# Controller_Rev_2.net
KiCad netlist of a schematic drawn in EAGLE
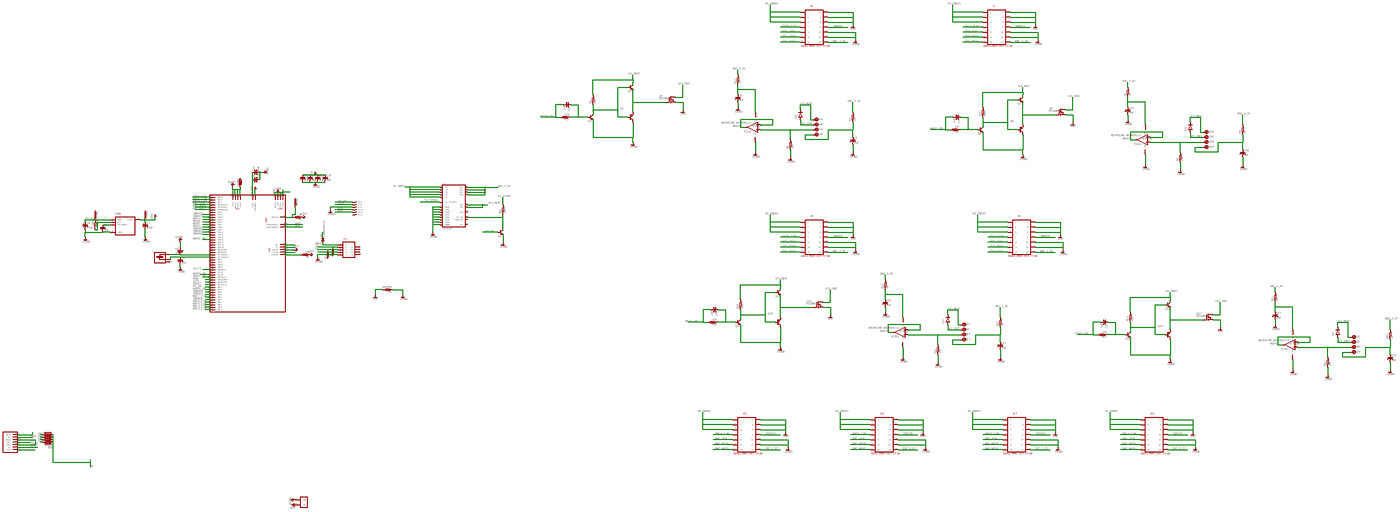
[diagram p0: schematic, sheet 1, overview]
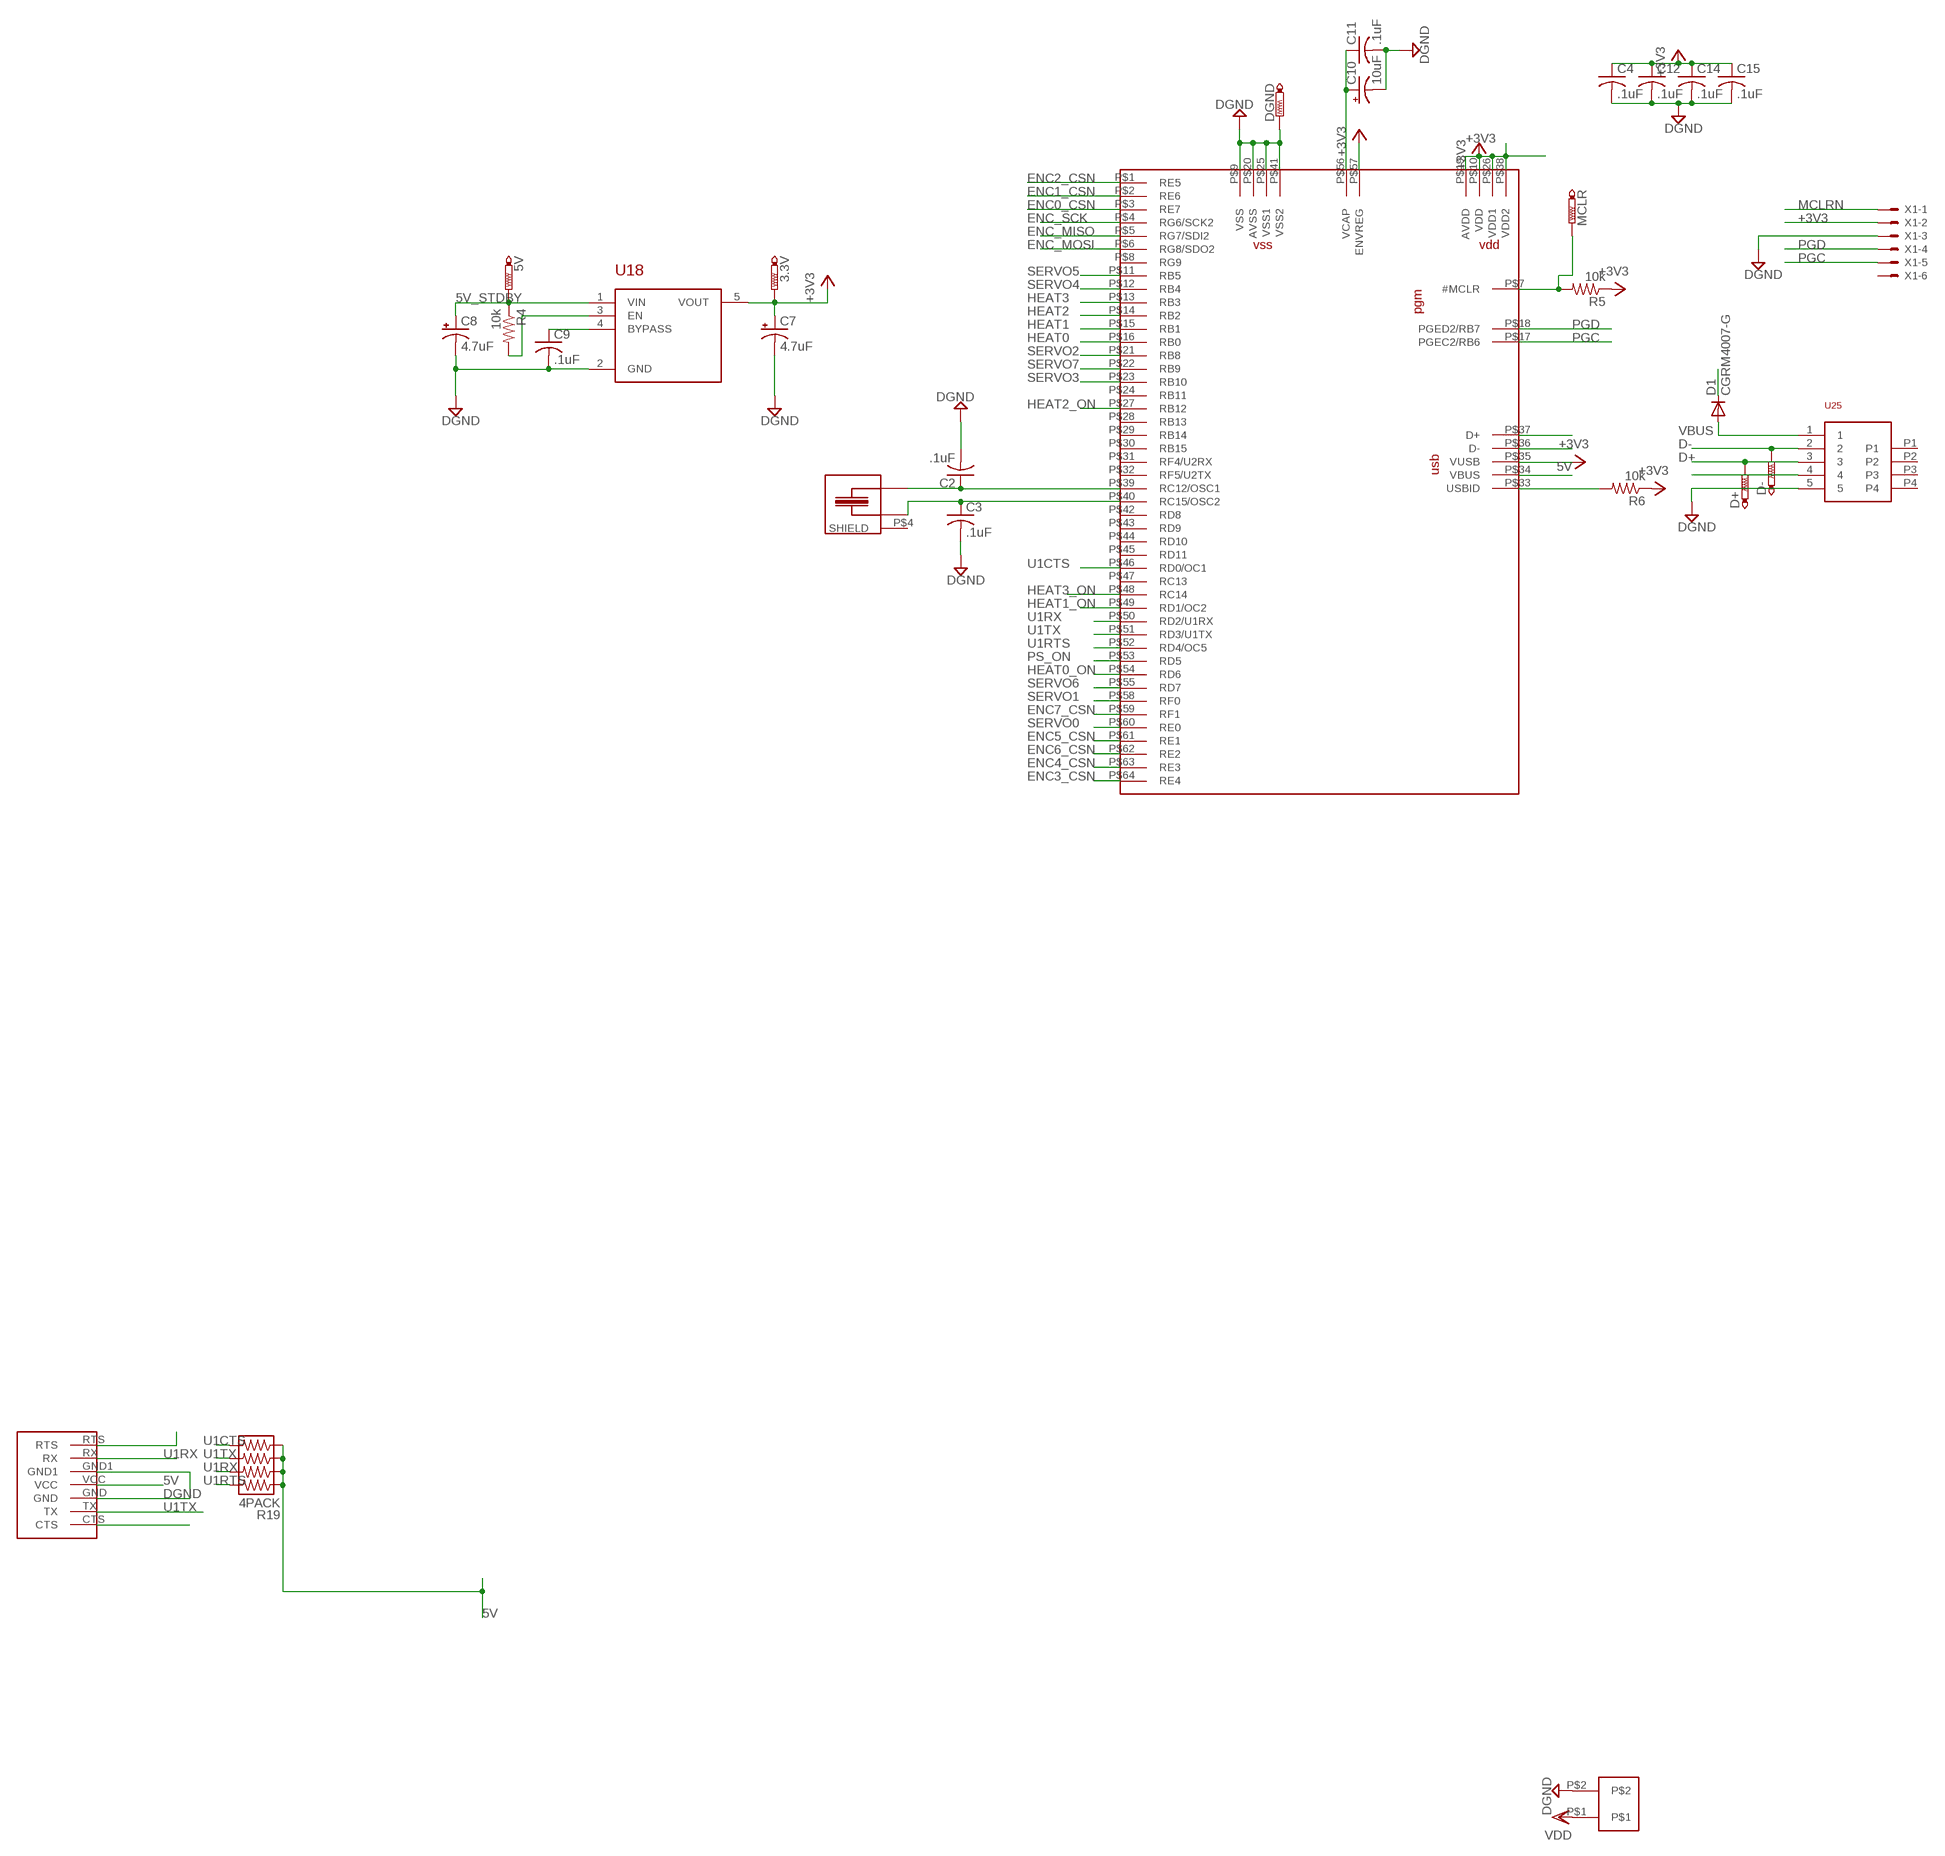
[diagram p1: schematic, sheet 1, part 1 of 4]
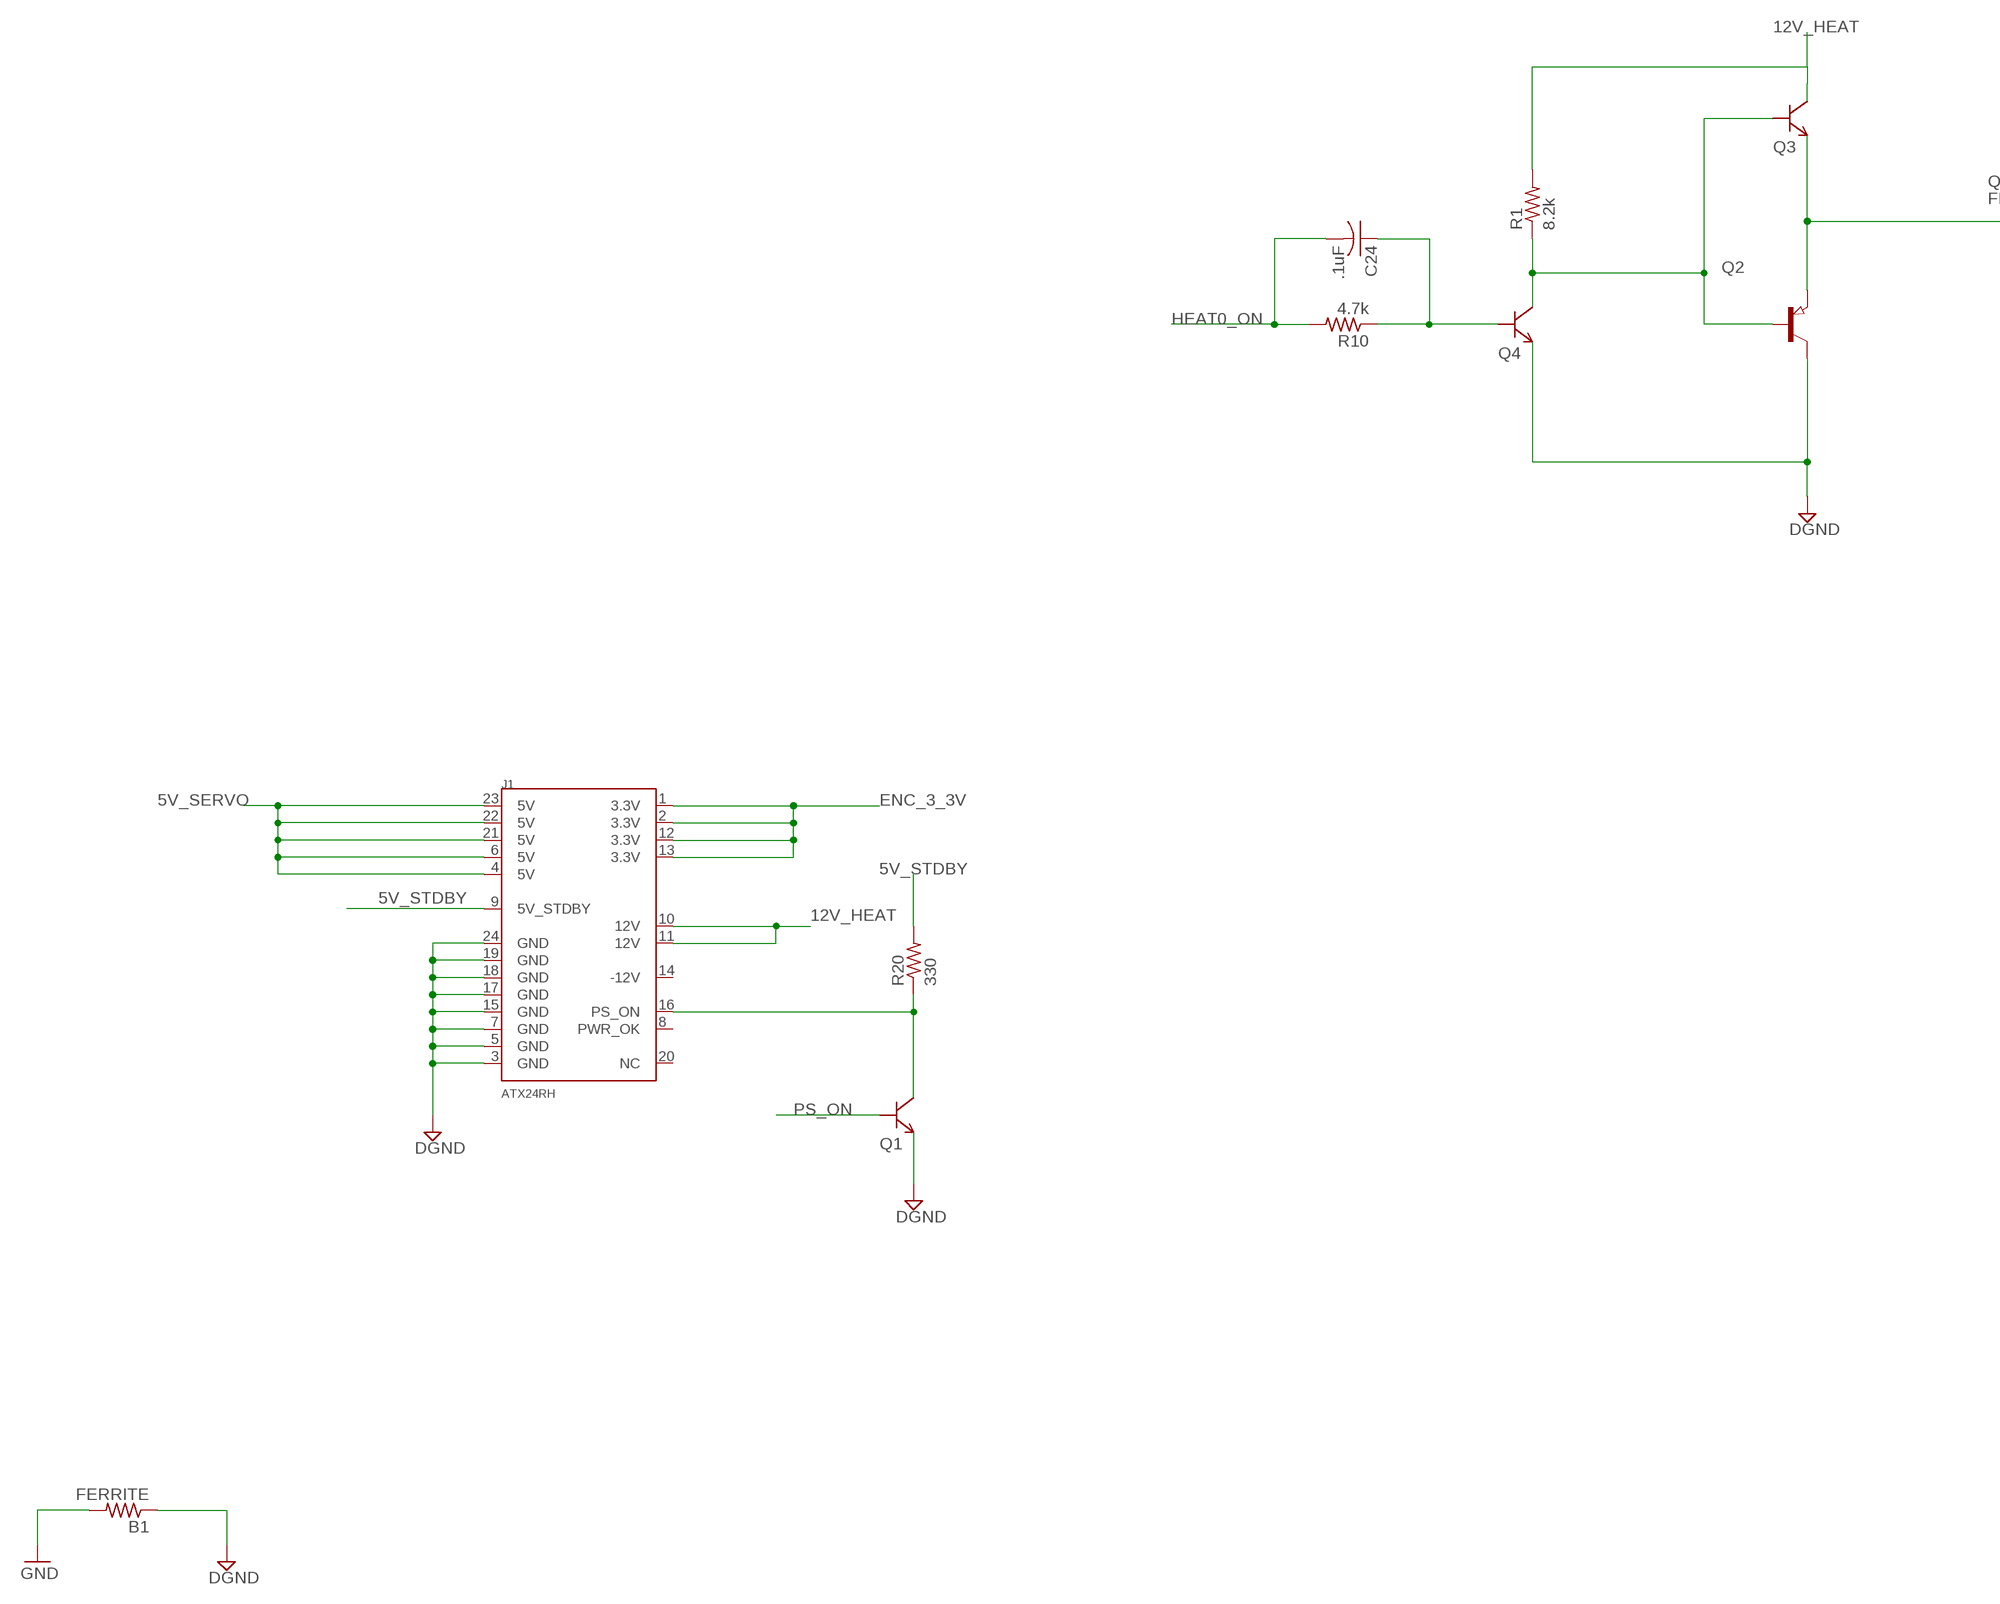
[diagram p2: schematic, sheet 1, part 2 of 4]
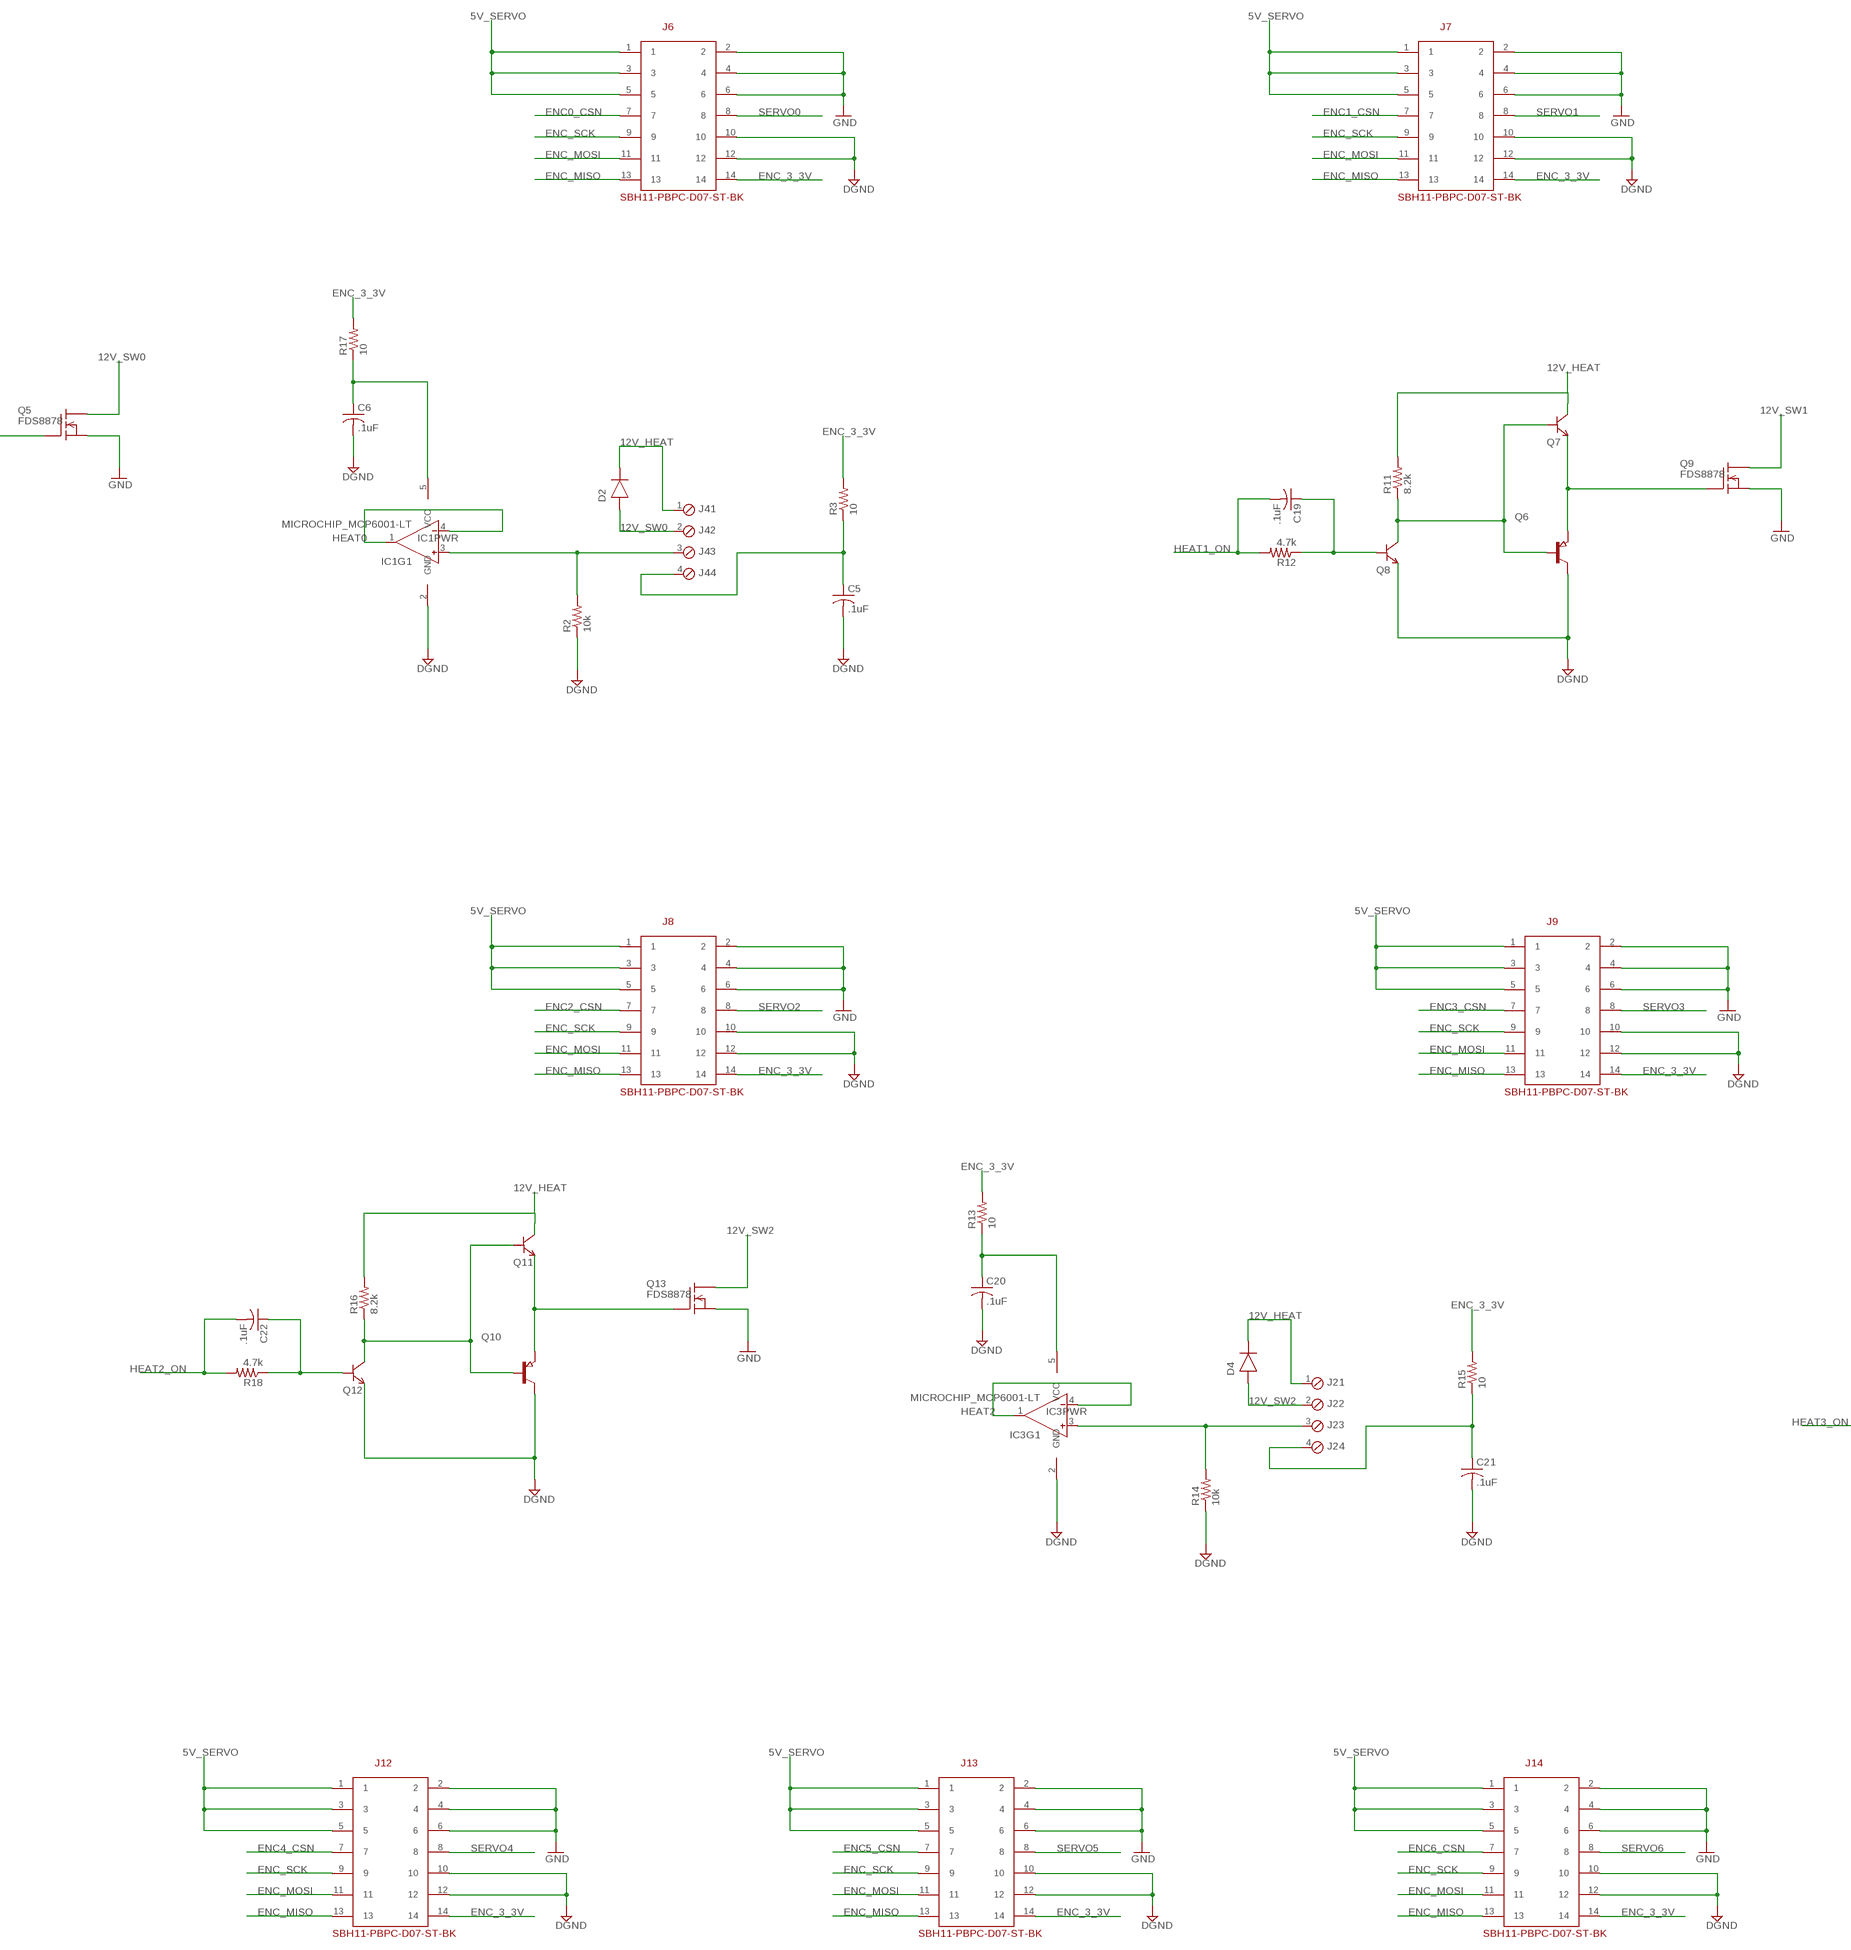
[diagram p3: schematic, sheet 1, part 3 of 4]
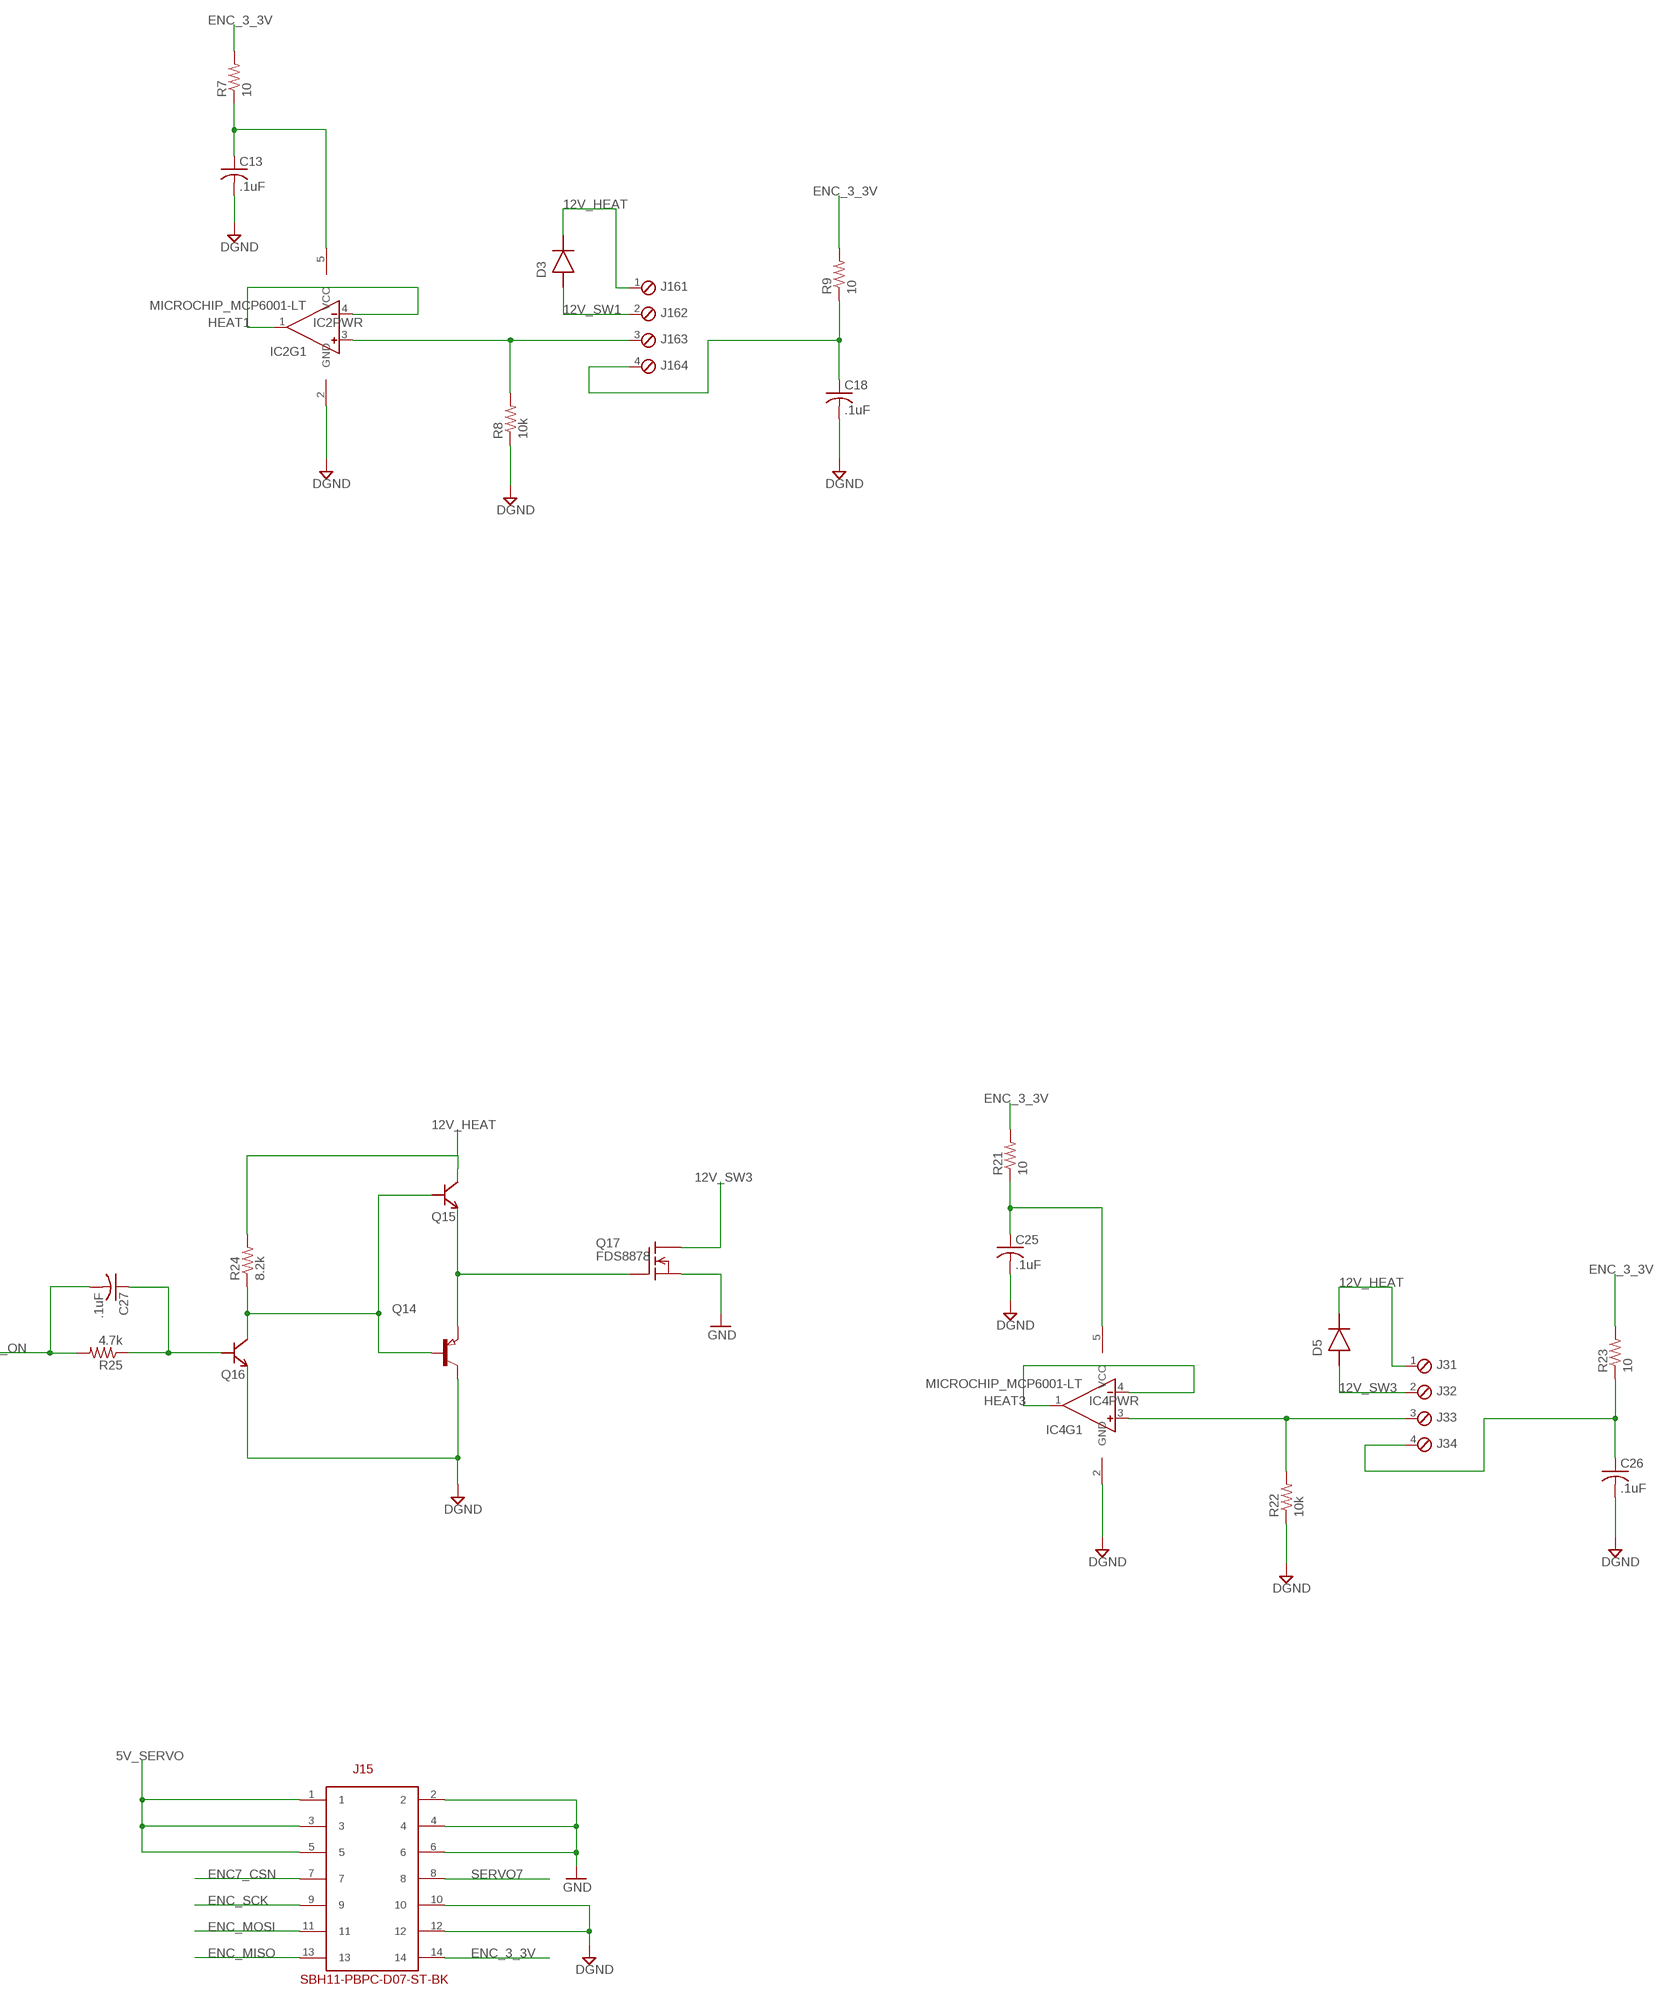
[diagram p4: schematic, sheet 1, part 4 of 4]

(export (version "E")
  (design (tool "Eeschema 10.0.6"))
  (components
    (comp (ref "3.3V")
      (value "PTR1TP14R")
      (footprint "eagle-import:TP14R")
      (libsource (lib "eagle-import") (part "PTR1TP14R"))
    )
    (comp (ref "5V")
      (value "PTR1TP14R")
      (footprint "eagle-import:TP14R")
      (libsource (lib "eagle-import") (part "PTR1TP14R"))
    )
    (comp (ref "B1")
      (value "FERRITE")
      (footprint "eagle-import:R0603")
      (libsource (lib "eagle-import") (part "R-US_R0603"))
    )
    (comp (ref "C2")
      (value ".1uF")
      (footprint "eagle-import:C0603")
      (libsource (lib "eagle-import") (part "C-USC0603"))
    )
    (comp (ref "C3")
      (value ".1uF")
      (footprint "eagle-import:C0603")
      (libsource (lib "eagle-import") (part "C-USC0603"))
    )
    (comp (ref "C4")
      (value ".1uF")
      (footprint "eagle-import:C0603")
      (libsource (lib "eagle-import") (part "C-USC0603"))
    )
    (comp (ref "C5")
      (value ".1uF")
      (footprint "eagle-import:C0603")
      (libsource (lib "eagle-import") (part "C-USC0603"))
    )
    (comp (ref "C6")
      (value ".1uF")
      (footprint "eagle-import:C0603")
      (libsource (lib "eagle-import") (part "C-USC0603"))
    )
    (comp (ref "C7")
      (value "4.7uF")
      (footprint "eagle-import:R_2012-12R")
      (libsource (lib "eagle-import") (part "CPOL-USR/2012-12R"))
    )
    (comp (ref "C8")
      (value "4.7uF")
      (footprint "eagle-import:R_2012-12R")
      (libsource (lib "eagle-import") (part "CPOL-USR/2012-12R"))
    )
    (comp (ref "C9")
      (value ".1uF")
      (footprint "eagle-import:C0402")
      (libsource (lib "eagle-import") (part "C-USC0402"))
    )
    (comp (ref "C10")
      (value "10uF")
      (footprint "eagle-import:R_2012-12R")
      (libsource (lib "eagle-import") (part "CPOL-USR/2012-12R"))
    )
    (comp (ref "C11")
      (value ".1uF")
      (footprint "eagle-import:C0603")
      (libsource (lib "eagle-import") (part "C-USC0603"))
    )
    (comp (ref "C12")
      (value ".1uF")
      (footprint "eagle-import:C0603")
      (libsource (lib "eagle-import") (part "C-USC0603"))
    )
    (comp (ref "C13")
      (value ".1uF")
      (footprint "eagle-import:C0603")
      (libsource (lib "eagle-import") (part "C-USC0603"))
    )
    (comp (ref "C14")
      (value ".1uF")
      (footprint "eagle-import:C0603")
      (libsource (lib "eagle-import") (part "C-USC0603"))
    )
    (comp (ref "C15")
      (value ".1uF")
      (footprint "eagle-import:C0603")
      (libsource (lib "eagle-import") (part "C-USC0603"))
    )
    (comp (ref "C18")
      (value ".1uF")
      (footprint "eagle-import:C0603")
      (libsource (lib "eagle-import") (part "C-USC0603"))
    )
    (comp (ref "C19")
      (value ".1uF")
      (footprint "eagle-import:C0603")
      (libsource (lib "eagle-import") (part "C-USC0603"))
    )
    (comp (ref "C20")
      (value ".1uF")
      (footprint "eagle-import:C0603")
      (libsource (lib "eagle-import") (part "C-USC0603"))
    )
    (comp (ref "C21")
      (value ".1uF")
      (footprint "eagle-import:C0603")
      (libsource (lib "eagle-import") (part "C-USC0603"))
    )
    (comp (ref "C22")
      (value ".1uF")
      (footprint "eagle-import:C0603")
      (libsource (lib "eagle-import") (part "C-USC0603"))
    )
    (comp (ref "C24")
      (value ".1uF")
      (footprint "eagle-import:C0603")
      (libsource (lib "eagle-import") (part "C-USC0603"))
    )
    (comp (ref "C25")
      (value ".1uF")
      (footprint "eagle-import:C0603")
      (libsource (lib "eagle-import") (part "C-USC0603"))
    )
    (comp (ref "C26")
      (value ".1uF")
      (footprint "eagle-import:C0603")
      (libsource (lib "eagle-import") (part "C-USC0603"))
    )
    (comp (ref "C27")
      (value ".1uF")
      (footprint "eagle-import:C0603")
      (libsource (lib "eagle-import") (part "C-USC0603"))
    )
    (comp (ref "D+")
      (value "PTR1TP14R")
      (footprint "eagle-import:TP14R")
      (libsource (lib "eagle-import") (part "PTR1TP14R"))
    )
    (comp (ref "D-")
      (value "PTR1TP14R")
      (footprint "eagle-import:TP14R")
      (libsource (lib "eagle-import") (part "PTR1TP14R"))
    )
    (comp (ref "D1")
      (value "CGRM4007-G")
      (footprint "eagle-import:SOD-123_MINI-SMA")
      (libsource (lib "eagle-import") (part "CGRM400-G7"))
    )
    (comp (ref "D2")
      (value "DISCRETE_DIODESMA")
      (footprint "eagle-import:DISCRETE_SMA")
      (libsource (lib "eagle-import") (part "DISCRETE_DIODESMA"))
    )
    (comp (ref "D3")
      (value "DISCRETE_DIODESMA")
      (footprint "eagle-import:DISCRETE_SMA")
      (libsource (lib "eagle-import") (part "DISCRETE_DIODESMA"))
    )
    (comp (ref "D4")
      (value "DISCRETE_DIODESMA")
      (footprint "eagle-import:DISCRETE_SMA")
      (libsource (lib "eagle-import") (part "DISCRETE_DIODESMA"))
    )
    (comp (ref "D5")
      (value "DISCRETE_DIODESMA")
      (footprint "eagle-import:DISCRETE_SMA")
      (libsource (lib "eagle-import") (part "DISCRETE_DIODESMA"))
    )
    (comp (ref "DGND")
      (value "PTR1B1,27")
      (footprint "eagle-import:B1,27")
      (libsource (lib "eagle-import") (part "PTR1B1,27"))
    )
    (comp (ref "IC1")
      (value "MICROCHIP_MCP6001-LT")
      (footprint "eagle-import:MICROCHIP_SC70-5-LT")
      (libsource (lib "eagle-import") (part "MICROCHIP_MCP6001-LT"))
    )
    (comp (ref "IC2")
      (value "MICROCHIP_MCP6001-LT")
      (footprint "eagle-import:MICROCHIP_SC70-5-LT")
      (libsource (lib "eagle-import") (part "MICROCHIP_MCP6001-LT"))
    )
    (comp (ref "IC3")
      (value "MICROCHIP_MCP6001-LT")
      (footprint "eagle-import:MICROCHIP_SC70-5-LT")
      (libsource (lib "eagle-import") (part "MICROCHIP_MCP6001-LT"))
    )
    (comp (ref "IC4")
      (value "MICROCHIP_MCP6001-LT")
      (footprint "eagle-import:MICROCHIP_SC70-5-LT")
      (libsource (lib "eagle-import") (part "MICROCHIP_MCP6001-LT"))
    )
    (comp (ref "J1")
      (value "ATX24RH")
      (footprint "eagle-import:ATX24_RIGHT_ANGLE")
      (libsource (lib "eagle-import") (part "ATX24RH"))
    )
    (comp (ref "J2")
      (value "OSTVN04A150")
      (footprint "eagle-import:4POL254")
      (libsource (lib "eagle-import") (part "OSTVN04A150"))
    )
    (comp (ref "J3")
      (value "OSTVN04A150")
      (footprint "eagle-import:4POL254")
      (libsource (lib "eagle-import") (part "OSTVN04A150"))
    )
    (comp (ref "J4")
      (value "OSTVN04A150")
      (footprint "eagle-import:4POL254")
      (libsource (lib "eagle-import") (part "OSTVN04A150"))
    )
    (comp (ref "J6")
      (value "SBH11-PBPC-D07-ST-BK")
      (footprint "eagle-import:SBH11-PBPC-D07-ST-BK")
      (libsource (lib "eagle-import") (part "SBH11-PBPC-D07-ST-BK"))
    )
    (comp (ref "J7")
      (value "SBH11-PBPC-D07-ST-BK")
      (footprint "eagle-import:SBH11-PBPC-D07-ST-BK")
      (libsource (lib "eagle-import") (part "SBH11-PBPC-D07-ST-BK"))
    )
    (comp (ref "J8")
      (value "SBH11-PBPC-D07-ST-BK")
      (footprint "eagle-import:SBH11-PBPC-D07-ST-BK")
      (libsource (lib "eagle-import") (part "SBH11-PBPC-D07-ST-BK"))
    )
    (comp (ref "J9")
      (value "SBH11-PBPC-D07-ST-BK")
      (footprint "eagle-import:SBH11-PBPC-D07-ST-BK")
      (libsource (lib "eagle-import") (part "SBH11-PBPC-D07-ST-BK"))
    )
    (comp (ref "J10")
      (value "WASP7PIN")
      (footprint "eagle-import:WASP7PIN")
      (libsource (lib "eagle-import") (part "WASP7PIN"))
    )
    (comp (ref "J12")
      (value "SBH11-PBPC-D07-ST-BK")
      (footprint "eagle-import:SBH11-PBPC-D07-ST-BK")
      (libsource (lib "eagle-import") (part "SBH11-PBPC-D07-ST-BK"))
    )
    (comp (ref "J13")
      (value "SBH11-PBPC-D07-ST-BK")
      (footprint "eagle-import:SBH11-PBPC-D07-ST-BK")
      (libsource (lib "eagle-import") (part "SBH11-PBPC-D07-ST-BK"))
    )
    (comp (ref "J14")
      (value "SBH11-PBPC-D07-ST-BK")
      (footprint "eagle-import:SBH11-PBPC-D07-ST-BK")
      (libsource (lib "eagle-import") (part "SBH11-PBPC-D07-ST-BK"))
    )
    (comp (ref "J15")
      (value "SBH11-PBPC-D07-ST-BK")
      (footprint "eagle-import:SBH11-PBPC-D07-ST-BK")
      (libsource (lib "eagle-import") (part "SBH11-PBPC-D07-ST-BK"))
    )
    (comp (ref "J16")
      (value "OSTVN04A150")
      (footprint "eagle-import:4POL254")
      (libsource (lib "eagle-import") (part "OSTVN04A150"))
    )
    (comp (ref "MCLR")
      (value "PTR1TP14R")
      (footprint "eagle-import:TP14R")
      (libsource (lib "eagle-import") (part "PTR1TP14R"))
    )
    (comp (ref "Q1")
      (value "DISCRETE_MMBT3904LT1G")
      (footprint "eagle-import:DISCRETE_SOT23")
      (libsource (lib "eagle-import") (part "DISCRETE_MMBT3904LT1G"))
    )
    (comp (ref "Q2")
      (value "PNP-TRANSISTOR_SOT23")
      (footprint "eagle-import:SOT23")
      (libsource (lib "eagle-import") (part "PNP-TRANSISTOR_SOT23"))
    )
    (comp (ref "Q3")
      (value "DISCRETE_MMBT3904LT1G")
      (footprint "eagle-import:DISCRETE_SOT23")
      (libsource (lib "eagle-import") (part "DISCRETE_MMBT3904LT1G"))
    )
    (comp (ref "Q4")
      (value "DISCRETE_MMBT3904LT1G")
      (footprint "eagle-import:DISCRETE_SOT23")
      (libsource (lib "eagle-import") (part "DISCRETE_MMBT3904LT1G"))
    )
    (comp (ref "Q5")
      (value "FDS8878")
      (footprint "eagle-import:SO-8")
      (libsource (lib "eagle-import") (part "FDS5680"))
    )
    (comp (ref "Q6")
      (value "PNP-TRANSISTOR_SOT23")
      (footprint "eagle-import:SOT23")
      (libsource (lib "eagle-import") (part "PNP-TRANSISTOR_SOT23"))
    )
    (comp (ref "Q7")
      (value "DISCRETE_MMBT3904LT1G")
      (footprint "eagle-import:DISCRETE_SOT23")
      (libsource (lib "eagle-import") (part "DISCRETE_MMBT3904LT1G"))
    )
    (comp (ref "Q8")
      (value "DISCRETE_MMBT3904LT1G")
      (footprint "eagle-import:DISCRETE_SOT23")
      (libsource (lib "eagle-import") (part "DISCRETE_MMBT3904LT1G"))
    )
    (comp (ref "Q9")
      (value "FDS8878")
      (footprint "eagle-import:SO-8")
      (libsource (lib "eagle-import") (part "FDS5680"))
    )
    (comp (ref "Q10")
      (value "PNP-TRANSISTOR_SOT23")
      (footprint "eagle-import:SOT23")
      (libsource (lib "eagle-import") (part "PNP-TRANSISTOR_SOT23"))
    )
    (comp (ref "Q11")
      (value "DISCRETE_MMBT3904LT1G")
      (footprint "eagle-import:DISCRETE_SOT23")
      (libsource (lib "eagle-import") (part "DISCRETE_MMBT3904LT1G"))
    )
    (comp (ref "Q12")
      (value "DISCRETE_MMBT3904LT1G")
      (footprint "eagle-import:DISCRETE_SOT23")
      (libsource (lib "eagle-import") (part "DISCRETE_MMBT3904LT1G"))
    )
    (comp (ref "Q13")
      (value "FDS8878")
      (footprint "eagle-import:SO-8")
      (libsource (lib "eagle-import") (part "FDS5680"))
    )
    (comp (ref "Q14")
      (value "PNP-TRANSISTOR_SOT23")
      (footprint "eagle-import:SOT23")
      (libsource (lib "eagle-import") (part "PNP-TRANSISTOR_SOT23"))
    )
    (comp (ref "Q15")
      (value "DISCRETE_MMBT3904LT1G")
      (footprint "eagle-import:DISCRETE_SOT23")
      (libsource (lib "eagle-import") (part "DISCRETE_MMBT3904LT1G"))
    )
    (comp (ref "Q16")
      (value "DISCRETE_MMBT3904LT1G")
      (footprint "eagle-import:DISCRETE_SOT23")
      (libsource (lib "eagle-import") (part "DISCRETE_MMBT3904LT1G"))
    )
    (comp (ref "Q17")
      (value "FDS8878")
      (footprint "eagle-import:SO-8")
      (libsource (lib "eagle-import") (part "FDS5680"))
    )
    (comp (ref "R1")
      (value "8.2k")
      (footprint "eagle-import:R0603")
      (libsource (lib "eagle-import") (part "R-US_R0603"))
    )
    (comp (ref "R2")
      (value "10k")
      (footprint "eagle-import:R0603")
      (libsource (lib "eagle-import") (part "R-US_R0603"))
    )
    (comp (ref "R3")
      (value "10")
      (footprint "eagle-import:R0603")
      (libsource (lib "eagle-import") (part "R-US_R0603"))
    )
    (comp (ref "R4")
      (value "10k")
      (footprint "eagle-import:R0402")
      (libsource (lib "eagle-import") (part "R-US_R0402"))
    )
    (comp (ref "R5")
      (value "10k")
      (footprint "eagle-import:R0603")
      (libsource (lib "eagle-import") (part "R-US_R0603"))
    )
    (comp (ref "R6")
      (value "10k")
      (footprint "eagle-import:R0603")
      (libsource (lib "eagle-import") (part "R-US_R0603"))
    )
    (comp (ref "R7")
      (value "10")
      (footprint "eagle-import:R0603")
      (libsource (lib "eagle-import") (part "R-US_R0603"))
    )
    (comp (ref "R8")
      (value "10k")
      (footprint "eagle-import:R0603")
      (libsource (lib "eagle-import") (part "R-US_R0603"))
    )
    (comp (ref "R9")
      (value "10")
      (footprint "eagle-import:R0603")
      (libsource (lib "eagle-import") (part "R-US_R0603"))
    )
    (comp (ref "R10")
      (value "4.7k")
      (footprint "eagle-import:R0603")
      (libsource (lib "eagle-import") (part "R-US_R0603"))
    )
    (comp (ref "R11")
      (value "8.2k")
      (footprint "eagle-import:R0603")
      (libsource (lib "eagle-import") (part "R-US_R0603"))
    )
    (comp (ref "R12")
      (value "4.7k")
      (footprint "eagle-import:R0603")
      (libsource (lib "eagle-import") (part "R-US_R0603"))
    )
    (comp (ref "R13")
      (value "10")
      (footprint "eagle-import:R0603")
      (libsource (lib "eagle-import") (part "R-US_R0603"))
    )
    (comp (ref "R14")
      (value "10k")
      (footprint "eagle-import:R0603")
      (libsource (lib "eagle-import") (part "R-US_R0603"))
    )
    (comp (ref "R15")
      (value "10")
      (footprint "eagle-import:R0603")
      (libsource (lib "eagle-import") (part "R-US_R0603"))
    )
    (comp (ref "R16")
      (value "8.2k")
      (footprint "eagle-import:R0603")
      (libsource (lib "eagle-import") (part "R-US_R0603"))
    )
    (comp (ref "R17")
      (value "10")
      (footprint "eagle-import:R0603")
      (libsource (lib "eagle-import") (part "R-US_R0603"))
    )
    (comp (ref "R18")
      (value "4.7k")
      (footprint "eagle-import:R0603")
      (libsource (lib "eagle-import") (part "R-US_R0603"))
    )
    (comp (ref "R19")
      (value "4PACK")
      (footprint "eagle-import:4PACK_0603")
      (libsource (lib "eagle-import") (part "4PACK"))
    )
    (comp (ref "R20")
      (value "330")
      (footprint "eagle-import:R0603")
      (libsource (lib "eagle-import") (part "R-US_R0603"))
    )
    (comp (ref "R21")
      (value "10")
      (footprint "eagle-import:R0603")
      (libsource (lib "eagle-import") (part "R-US_R0603"))
    )
    (comp (ref "R22")
      (value "10k")
      (footprint "eagle-import:R0603")
      (libsource (lib "eagle-import") (part "R-US_R0603"))
    )
    (comp (ref "R23")
      (value "10")
      (footprint "eagle-import:R0603")
      (libsource (lib "eagle-import") (part "R-US_R0603"))
    )
    (comp (ref "R24")
      (value "8.2k")
      (footprint "eagle-import:R0603")
      (libsource (lib "eagle-import") (part "R-US_R0603"))
    )
    (comp (ref "R25")
      (value "4.7k")
      (footprint "eagle-import:R0603")
      (libsource (lib "eagle-import") (part "R-US_R0603"))
    )
    (comp (ref "U$19")
      (value "2P")
      (footprint "eagle-import:2PTH")
      (libsource (lib "eagle-import") (part "2P"))
    )
    (comp (ref "U3")
      (value "PIC32-64TQFP64-2")
      (footprint "eagle-import:TQFP64-2")
      (libsource (lib "eagle-import") (part "PIC32-64TQFP64-2"))
    )
    (comp (ref "U18")
      (value "LDS3985XX33")
      (footprint "eagle-import:SOT23-5")
      (libsource (lib "eagle-import") (part "LDS3985XX33"))
    )
    (comp (ref "U25")
      (value "1734035-1_USB")
      (footprint "eagle-import:1734035-1_1734035")
      (libsource (lib "eagle-import") (part "1734035-1_USB"))
    )
    (comp (ref "X1")
      (value "22-23-2061")
      (footprint "eagle-import:22-23-2061")
      (fields (field (name "MF") "MOLEX"))
      (libsource (lib "eagle-import") (part "22-23-2061"))
    )
    (comp (ref "X2")
      (value "CMR3XXT")
      (footprint "eagle-import:CMR309T")
      (libsource (lib "eagle-import") (part "CMR3XXT"))
    )
  )
  (nets
    (net (code "1") (name "+3V3") (class "Default")
      (node (ref "3.3V") (pin "TP") (pinfunction "TP_TP") (pintype "input"))
      (node (ref "C12") (pin "1") (pinfunction "1_1") (pintype "passive"))
      (node (ref "C14") (pin "1") (pinfunction "1_1") (pintype "passive"))
      (node (ref "C15") (pin "1") (pinfunction "1_1") (pintype "passive"))
      (node (ref "C4") (pin "1") (pinfunction "1_1") (pintype "passive"))
      (node (ref "C7") (pin "+") (pinfunction "+_+") (pintype "passive"))
      (node (ref "R5") (pin "1") (pinfunction "1_1") (pintype "passive"))
      (node (ref "R6") (pin "1") (pinfunction "1_1") (pintype "passive"))
      (node (ref "U18") (pin "5") (pinfunction "VOUT_5") (pintype "bidirectional"))
      (node (ref "U3") (pin "P$10") (pinfunction "VDD_P$10") (pintype "bidirectional"))
      (node (ref "U3") (pin "P$19") (pinfunction "AVDD_P$19") (pintype "bidirectional"))
      (node (ref "U3") (pin "P$26") (pinfunction "VDD1_P$26") (pintype "bidirectional"))
      (node (ref "U3") (pin "P$35") (pinfunction "VUSB_P$35") (pintype "bidirectional"))
      (node (ref "U3") (pin "P$38") (pinfunction "VDD2_P$38") (pintype "bidirectional"))
      (node (ref "U3") (pin "P$57") (pinfunction "ENVREG_P$57") (pintype "bidirectional"))
      (node (ref "X1") (pin "2") (pinfunction "S_2") (pintype "passive"))
    )
    (net (code "2") (name "/5V") (class "Default")
      (node (ref "D1") (pin "C") (pinfunction "C_C") (pintype "passive"))
      (node (ref "J10") (pin "VCC") (pinfunction "VCC_VCC") (pintype "bidirectional"))
      (node (ref "R19") (pin "R1B") (pinfunction "R1B_R1B") (pintype "passive"))
      (node (ref "R19") (pin "R2B") (pinfunction "R2B_R2B") (pintype "passive"))
      (node (ref "R19") (pin "R3B") (pinfunction "R3B_R3B") (pintype "passive"))
      (node (ref "R19") (pin "R4B") (pinfunction "R4B_R4B") (pintype "passive"))
      (node (ref "U3") (pin "P$34") (pinfunction "VBUS_P$34") (pintype "bidirectional"))
    )
    (net (code "3") (name "/5V_SERVO") (class "Default")
      (node (ref "J1") (pin "21") (pinfunction "5V_21") (pintype "bidirectional"))
      (node (ref "J1") (pin "22") (pinfunction "5V_22") (pintype "bidirectional"))
      (node (ref "J1") (pin "23") (pinfunction "5V_23") (pintype "bidirectional"))
      (node (ref "J1") (pin "4") (pinfunction "5V_4") (pintype "bidirectional"))
      (node (ref "J1") (pin "6") (pinfunction "5V_6") (pintype "bidirectional"))
      (node (ref "J12") (pin "1") (pinfunction "1_1") (pintype "bidirectional"))
      (node (ref "J12") (pin "3") (pinfunction "3_3") (pintype "bidirectional"))
      (node (ref "J12") (pin "5") (pinfunction "5_5") (pintype "bidirectional"))
      (node (ref "J13") (pin "1") (pinfunction "1_1") (pintype "bidirectional"))
      (node (ref "J13") (pin "3") (pinfunction "3_3") (pintype "bidirectional"))
      (node (ref "J13") (pin "5") (pinfunction "5_5") (pintype "bidirectional"))
      (node (ref "J14") (pin "1") (pinfunction "1_1") (pintype "bidirectional"))
      (node (ref "J14") (pin "3") (pinfunction "3_3") (pintype "bidirectional"))
      (node (ref "J14") (pin "5") (pinfunction "5_5") (pintype "bidirectional"))
      (node (ref "J15") (pin "1") (pinfunction "1_1") (pintype "bidirectional"))
      (node (ref "J15") (pin "3") (pinfunction "3_3") (pintype "bidirectional"))
      (node (ref "J15") (pin "5") (pinfunction "5_5") (pintype "bidirectional"))
      (node (ref "J6") (pin "1") (pinfunction "1_1") (pintype "bidirectional"))
      (node (ref "J6") (pin "3") (pinfunction "3_3") (pintype "bidirectional"))
      (node (ref "J6") (pin "5") (pinfunction "5_5") (pintype "bidirectional"))
      (node (ref "J7") (pin "1") (pinfunction "1_1") (pintype "bidirectional"))
      (node (ref "J7") (pin "3") (pinfunction "3_3") (pintype "bidirectional"))
      (node (ref "J7") (pin "5") (pinfunction "5_5") (pintype "bidirectional"))
      (node (ref "J8") (pin "1") (pinfunction "1_1") (pintype "bidirectional"))
      (node (ref "J8") (pin "3") (pinfunction "3_3") (pintype "bidirectional"))
      (node (ref "J8") (pin "5") (pinfunction "5_5") (pintype "bidirectional"))
      (node (ref "J9") (pin "1") (pinfunction "1_1") (pintype "bidirectional"))
      (node (ref "J9") (pin "3") (pinfunction "3_3") (pintype "bidirectional"))
      (node (ref "J9") (pin "5") (pinfunction "5_5") (pintype "bidirectional"))
    )
    (net (code "4") (name "/5V_STDBY") (class "Default")
      (node (ref "5V") (pin "TP") (pinfunction "TP_TP") (pintype "input"))
      (node (ref "C8") (pin "+") (pinfunction "+_+") (pintype "passive"))
      (node (ref "J1") (pin "9") (pinfunction "5V_STDBY_9") (pintype "bidirectional"))
      (node (ref "R20") (pin "2") (pinfunction "2_2") (pintype "passive"))
      (node (ref "R4") (pin "1") (pinfunction "1_1") (pintype "passive"))
      (node (ref "U18") (pin "1") (pinfunction "VIN_1") (pintype "bidirectional"))
    )
    (net (code "5") (name "/12V_HEAT") (class "Default")
      (node (ref "D2") (pin "C") (pinfunction "C_C") (pintype "bidirectional"))
      (node (ref "D3") (pin "C") (pinfunction "C_C") (pintype "bidirectional"))
      (node (ref "D4") (pin "C") (pinfunction "C_C") (pintype "bidirectional"))
      (node (ref "D5") (pin "C") (pinfunction "C_C") (pintype "bidirectional"))
      (node (ref "J1") (pin "10") (pinfunction "12V_10") (pintype "bidirectional"))
      (node (ref "J1") (pin "11") (pinfunction "12V_11") (pintype "bidirectional"))
      (node (ref "J16") (pin "1") (pinfunction "1_1") (pintype "passive"))
      (node (ref "J2") (pin "1") (pinfunction "1_1") (pintype "passive"))
      (node (ref "J3") (pin "1") (pinfunction "1_1") (pintype "passive"))
      (node (ref "J4") (pin "1") (pinfunction "1_1") (pintype "passive"))
      (node (ref "Q11") (pin "3") (pinfunction "C_3") (pintype "bidirectional"))
      (node (ref "Q15") (pin "3") (pinfunction "C_3") (pintype "bidirectional"))
      (node (ref "Q3") (pin "3") (pinfunction "C_3") (pintype "bidirectional"))
      (node (ref "Q7") (pin "3") (pinfunction "C_3") (pintype "bidirectional"))
      (node (ref "R1") (pin "2") (pinfunction "2_2") (pintype "passive"))
      (node (ref "R11") (pin "2") (pinfunction "2_2") (pintype "passive"))
      (node (ref "R16") (pin "2") (pinfunction "2_2") (pintype "passive"))
      (node (ref "R24") (pin "2") (pinfunction "2_2") (pintype "passive"))
    )
    (net (code "6") (name "/12V_SW0") (class "Default")
      (node (ref "D2") (pin "A") (pinfunction "A_A") (pintype "bidirectional"))
      (node (ref "J4") (pin "2") (pinfunction "1_2") (pintype "passive"))
      (node (ref "Q5") (pin "5") (pinfunction "D_5") (pintype "passive"))
      (node (ref "Q5") (pin "6") (pinfunction "D_6") (pintype "passive"))
      (node (ref "Q5") (pin "7") (pinfunction "D_7") (pintype "passive"))
      (node (ref "Q5") (pin "8") (pinfunction "D_8") (pintype "passive"))
    )
    (net (code "7") (name "/12V_SW1") (class "Default")
      (node (ref "D3") (pin "A") (pinfunction "A_A") (pintype "bidirectional"))
      (node (ref "J16") (pin "2") (pinfunction "1_2") (pintype "passive"))
      (node (ref "Q9") (pin "5") (pinfunction "D_5") (pintype "passive"))
      (node (ref "Q9") (pin "6") (pinfunction "D_6") (pintype "passive"))
      (node (ref "Q9") (pin "7") (pinfunction "D_7") (pintype "passive"))
      (node (ref "Q9") (pin "8") (pinfunction "D_8") (pintype "passive"))
    )
    (net (code "8") (name "/12V_SW2") (class "Default")
      (node (ref "D4") (pin "A") (pinfunction "A_A") (pintype "bidirectional"))
      (node (ref "J2") (pin "2") (pinfunction "1_2") (pintype "passive"))
      (node (ref "Q13") (pin "5") (pinfunction "D_5") (pintype "passive"))
      (node (ref "Q13") (pin "6") (pinfunction "D_6") (pintype "passive"))
      (node (ref "Q13") (pin "7") (pinfunction "D_7") (pintype "passive"))
      (node (ref "Q13") (pin "8") (pinfunction "D_8") (pintype "passive"))
    )
    (net (code "9") (name "/12V_SW3") (class "Default")
      (node (ref "D5") (pin "A") (pinfunction "A_A") (pintype "bidirectional"))
      (node (ref "J3") (pin "2") (pinfunction "1_2") (pintype "passive"))
      (node (ref "Q17") (pin "5") (pinfunction "D_5") (pintype "passive"))
      (node (ref "Q17") (pin "6") (pinfunction "D_6") (pintype "passive"))
      (node (ref "Q17") (pin "7") (pinfunction "D_7") (pintype "passive"))
      (node (ref "Q17") (pin "8") (pinfunction "D_8") (pintype "passive"))
    )
    (net (code "10") (name "/D+") (class "Default")
      (node (ref "D+") (pin "TP") (pinfunction "TP_TP") (pintype "input"))
      (node (ref "U25") (pin "3") (pinfunction "3_3") (pintype "bidirectional"))
      (node (ref "U3") (pin "P$37") (pinfunction "D+_P$37") (pintype "bidirectional"))
    )
    (net (code "11") (name "/D-") (class "Default")
      (node (ref "D-") (pin "TP") (pinfunction "TP_TP") (pintype "input"))
      (node (ref "U25") (pin "2") (pinfunction "2_2") (pintype "bidirectional"))
      (node (ref "U3") (pin "P$36") (pinfunction "D-_P$36") (pintype "bidirectional"))
    )
    (net (code "12") (name "/ENC0_CSN") (class "Default")
      (node (ref "J6") (pin "7") (pinfunction "7_7") (pintype "bidirectional"))
      (node (ref "U3") (pin "P$3") (pinfunction "RE7_P$3") (pintype "bidirectional"))
    )
    (net (code "13") (name "/ENC1_CSN") (class "Default")
      (node (ref "J7") (pin "7") (pinfunction "7_7") (pintype "bidirectional"))
      (node (ref "U3") (pin "P$2") (pinfunction "RE6_P$2") (pintype "bidirectional"))
    )
    (net (code "14") (name "/ENC2_CSN") (class "Default")
      (node (ref "J8") (pin "7") (pinfunction "7_7") (pintype "bidirectional"))
      (node (ref "U3") (pin "P$1") (pinfunction "RE5_P$1") (pintype "bidirectional"))
    )
    (net (code "15") (name "/ENC3_CSN") (class "Default")
      (node (ref "J9") (pin "7") (pinfunction "7_7") (pintype "bidirectional"))
      (node (ref "U3") (pin "P$64") (pinfunction "RE4_P$64") (pintype "bidirectional"))
    )
    (net (code "16") (name "/ENC4_CSN") (class "Default")
      (node (ref "J12") (pin "7") (pinfunction "7_7") (pintype "bidirectional"))
      (node (ref "U3") (pin "P$63") (pinfunction "RE3_P$63") (pintype "bidirectional"))
    )
    (net (code "17") (name "/ENC5_CSN") (class "Default")
      (node (ref "J13") (pin "7") (pinfunction "7_7") (pintype "bidirectional"))
      (node (ref "U3") (pin "P$61") (pinfunction "RE1_P$61") (pintype "bidirectional"))
    )
    (net (code "18") (name "/ENC6_CSN") (class "Default")
      (node (ref "J14") (pin "7") (pinfunction "7_7") (pintype "bidirectional"))
      (node (ref "U3") (pin "P$62") (pinfunction "RE2_P$62") (pintype "bidirectional"))
    )
    (net (code "19") (name "/ENC7_CSN") (class "Default")
      (node (ref "J15") (pin "7") (pinfunction "7_7") (pintype "bidirectional"))
      (node (ref "U3") (pin "P$59") (pinfunction "RF1_P$59") (pintype "bidirectional"))
    )
    (net (code "20") (name "/ENC_3_3V") (class "Default")
      (node (ref "J1") (pin "1") (pinfunction "3.3V_1") (pintype "bidirectional"))
      (node (ref "J1") (pin "12") (pinfunction "3.3V_12") (pintype "bidirectional"))
      (node (ref "J1") (pin "13") (pinfunction "3.3V_13") (pintype "bidirectional"))
      (node (ref "J1") (pin "2") (pinfunction "3.3V_2") (pintype "bidirectional"))
      (node (ref "J12") (pin "14") (pinfunction "14_14") (pintype "bidirectional"))
      (node (ref "J13") (pin "14") (pinfunction "14_14") (pintype "bidirectional"))
      (node (ref "J14") (pin "14") (pinfunction "14_14") (pintype "bidirectional"))
      (node (ref "J15") (pin "14") (pinfunction "14_14") (pintype "bidirectional"))
      (node (ref "J6") (pin "14") (pinfunction "14_14") (pintype "bidirectional"))
      (node (ref "J7") (pin "14") (pinfunction "14_14") (pintype "bidirectional"))
      (node (ref "J8") (pin "14") (pinfunction "14_14") (pintype "bidirectional"))
      (node (ref "J9") (pin "14") (pinfunction "14_14") (pintype "bidirectional"))
      (node (ref "R13") (pin "2") (pinfunction "2_2") (pintype "passive"))
      (node (ref "R15") (pin "2") (pinfunction "2_2") (pintype "passive"))
      (node (ref "R17") (pin "2") (pinfunction "2_2") (pintype "passive"))
      (node (ref "R21") (pin "2") (pinfunction "2_2") (pintype "passive"))
      (node (ref "R23") (pin "2") (pinfunction "2_2") (pintype "passive"))
      (node (ref "R3") (pin "2") (pinfunction "2_2") (pintype "passive"))
      (node (ref "R7") (pin "2") (pinfunction "2_2") (pintype "passive"))
      (node (ref "R9") (pin "2") (pinfunction "2_2") (pintype "passive"))
    )
    (net (code "21") (name "/ENC_MISO") (class "Default")
      (node (ref "J12") (pin "13") (pinfunction "13_13") (pintype "bidirectional"))
      (node (ref "J13") (pin "13") (pinfunction "13_13") (pintype "bidirectional"))
      (node (ref "J14") (pin "13") (pinfunction "13_13") (pintype "bidirectional"))
      (node (ref "J15") (pin "13") (pinfunction "13_13") (pintype "bidirectional"))
      (node (ref "J6") (pin "13") (pinfunction "13_13") (pintype "bidirectional"))
      (node (ref "J7") (pin "13") (pinfunction "13_13") (pintype "bidirectional"))
      (node (ref "J8") (pin "13") (pinfunction "13_13") (pintype "bidirectional"))
      (node (ref "J9") (pin "13") (pinfunction "13_13") (pintype "bidirectional"))
      (node (ref "U3") (pin "P$5") (pinfunction "RG7/SDI2_P$5") (pintype "bidirectional"))
    )
    (net (code "22") (name "/ENC_MOSI") (class "Default")
      (node (ref "J12") (pin "11") (pinfunction "11_11") (pintype "bidirectional"))
      (node (ref "J13") (pin "11") (pinfunction "11_11") (pintype "bidirectional"))
      (node (ref "J14") (pin "11") (pinfunction "11_11") (pintype "bidirectional"))
      (node (ref "J15") (pin "11") (pinfunction "11_11") (pintype "bidirectional"))
      (node (ref "J6") (pin "11") (pinfunction "11_11") (pintype "bidirectional"))
      (node (ref "J7") (pin "11") (pinfunction "11_11") (pintype "bidirectional"))
      (node (ref "J8") (pin "11") (pinfunction "11_11") (pintype "bidirectional"))
      (node (ref "J9") (pin "11") (pinfunction "11_11") (pintype "bidirectional"))
      (node (ref "U3") (pin "P$6") (pinfunction "RG8/SDO2_P$6") (pintype "bidirectional"))
    )
    (net (code "23") (name "/ENC_SCK") (class "Default")
      (node (ref "J12") (pin "9") (pinfunction "9_9") (pintype "bidirectional"))
      (node (ref "J13") (pin "9") (pinfunction "9_9") (pintype "bidirectional"))
      (node (ref "J14") (pin "9") (pinfunction "9_9") (pintype "bidirectional"))
      (node (ref "J15") (pin "9") (pinfunction "9_9") (pintype "bidirectional"))
      (node (ref "J6") (pin "9") (pinfunction "9_9") (pintype "bidirectional"))
      (node (ref "J7") (pin "9") (pinfunction "9_9") (pintype "bidirectional"))
      (node (ref "J8") (pin "9") (pinfunction "9_9") (pintype "bidirectional"))
      (node (ref "J9") (pin "9") (pinfunction "9_9") (pintype "bidirectional"))
      (node (ref "U3") (pin "P$4") (pinfunction "RG6/SCK2_P$4") (pintype "bidirectional"))
    )
    (net (code "24") (name "/HEAT0") (class "Default")
      (node (ref "IC1") (pin "1") (pinfunction "OUT_1") (pintype "output"))
      (node (ref "IC1") (pin "4") (pinfunction "IN-_4") (pintype "input"))
      (node (ref "U3") (pin "P$16") (pinfunction "RB0_P$16") (pintype "bidirectional"))
    )
    (net (code "25") (name "/HEAT0_ON") (class "Default")
      (node (ref "C24") (pin "2") (pinfunction "2_2") (pintype "passive"))
      (node (ref "R10") (pin "2") (pinfunction "2_2") (pintype "passive"))
      (node (ref "U3") (pin "P$54") (pinfunction "RD6_P$54") (pintype "bidirectional"))
    )
    (net (code "26") (name "/HEAT1") (class "Default")
      (node (ref "IC2") (pin "1") (pinfunction "OUT_1") (pintype "output"))
      (node (ref "IC2") (pin "4") (pinfunction "IN-_4") (pintype "input"))
      (node (ref "U3") (pin "P$15") (pinfunction "RB1_P$15") (pintype "bidirectional"))
    )
    (net (code "27") (name "/HEAT1_ON") (class "Default")
      (node (ref "C19") (pin "2") (pinfunction "2_2") (pintype "passive"))
      (node (ref "R12") (pin "2") (pinfunction "2_2") (pintype "passive"))
      (node (ref "U3") (pin "P$49") (pinfunction "RD1/OC2_P$49") (pintype "bidirectional"))
    )
    (net (code "28") (name "/HEAT2") (class "Default")
      (node (ref "IC3") (pin "1") (pinfunction "OUT_1") (pintype "output"))
      (node (ref "IC3") (pin "4") (pinfunction "IN-_4") (pintype "input"))
      (node (ref "U3") (pin "P$14") (pinfunction "RB2_P$14") (pintype "bidirectional"))
    )
    (net (code "29") (name "/HEAT2_ON") (class "Default")
      (node (ref "C22") (pin "2") (pinfunction "2_2") (pintype "passive"))
      (node (ref "R18") (pin "2") (pinfunction "2_2") (pintype "passive"))
      (node (ref "U3") (pin "P$27") (pinfunction "RB12_P$27") (pintype "bidirectional"))
    )
    (net (code "30") (name "/HEAT3") (class "Default")
      (node (ref "IC4") (pin "1") (pinfunction "OUT_1") (pintype "output"))
      (node (ref "IC4") (pin "4") (pinfunction "IN-_4") (pintype "input"))
      (node (ref "U3") (pin "P$13") (pinfunction "RB3_P$13") (pintype "bidirectional"))
    )
    (net (code "31") (name "/HEAT3_ON") (class "Default")
      (node (ref "C27") (pin "2") (pinfunction "2_2") (pintype "passive"))
      (node (ref "R25") (pin "2") (pinfunction "2_2") (pintype "passive"))
      (node (ref "U3") (pin "P$48") (pinfunction "RC14_P$48") (pintype "bidirectional"))
    )
    (net (code "32") (name "/MCLRN") (class "Default")
      (node (ref "MCLR") (pin "TP") (pinfunction "TP_TP") (pintype "input"))
      (node (ref "R5") (pin "2") (pinfunction "2_2") (pintype "passive"))
      (node (ref "U3") (pin "P$7") (pinfunction "#MCLR_P$7") (pintype "bidirectional"))
      (node (ref "X1") (pin "1") (pinfunction "S_1") (pintype "passive"))
    )
    (net (code "33") (name "/PGC") (class "Default")
      (node (ref "U3") (pin "P$17") (pinfunction "PGEC2/RB6_P$17") (pintype "bidirectional"))
      (node (ref "X1") (pin "5") (pinfunction "S_5") (pintype "passive"))
    )
    (net (code "34") (name "/PGD") (class "Default")
      (node (ref "U3") (pin "P$18") (pinfunction "PGED2/RB7_P$18") (pintype "bidirectional"))
      (node (ref "X1") (pin "4") (pinfunction "S_4") (pintype "passive"))
    )
    (net (code "35") (name "/PS_ON") (class "Default")
      (node (ref "Q1") (pin "1") (pinfunction "B_1") (pintype "bidirectional"))
      (node (ref "U3") (pin "P$53") (pinfunction "RD5_P$53") (pintype "bidirectional"))
    )
    (net (code "36") (name "/SERVO0") (class "Default")
      (node (ref "J6") (pin "8") (pinfunction "8_8") (pintype "bidirectional"))
      (node (ref "U3") (pin "P$60") (pinfunction "RE0_P$60") (pintype "bidirectional"))
    )
    (net (code "37") (name "/SERVO1") (class "Default")
      (node (ref "J7") (pin "8") (pinfunction "8_8") (pintype "bidirectional"))
      (node (ref "U3") (pin "P$58") (pinfunction "RF0_P$58") (pintype "bidirectional"))
    )
    (net (code "38") (name "/SERVO2") (class "Default")
      (node (ref "J8") (pin "8") (pinfunction "8_8") (pintype "bidirectional"))
      (node (ref "U3") (pin "P$21") (pinfunction "RB8_P$21") (pintype "bidirectional"))
    )
    (net (code "39") (name "/SERVO3") (class "Default")
      (node (ref "J9") (pin "8") (pinfunction "8_8") (pintype "bidirectional"))
      (node (ref "U3") (pin "P$23") (pinfunction "RB10_P$23") (pintype "bidirectional"))
    )
    (net (code "40") (name "/SERVO4") (class "Default")
      (node (ref "J12") (pin "8") (pinfunction "8_8") (pintype "bidirectional"))
      (node (ref "U3") (pin "P$12") (pinfunction "RB4_P$12") (pintype "bidirectional"))
    )
    (net (code "41") (name "/SERVO5") (class "Default")
      (node (ref "J13") (pin "8") (pinfunction "8_8") (pintype "bidirectional"))
      (node (ref "U3") (pin "P$11") (pinfunction "RB5_P$11") (pintype "bidirectional"))
    )
    (net (code "42") (name "/SERVO6") (class "Default")
      (node (ref "J14") (pin "8") (pinfunction "8_8") (pintype "bidirectional"))
      (node (ref "U3") (pin "P$55") (pinfunction "RD7_P$55") (pintype "bidirectional"))
    )
    (net (code "43") (name "/SERVO7") (class "Default")
      (node (ref "J15") (pin "8") (pinfunction "8_8") (pintype "bidirectional"))
      (node (ref "U3") (pin "P$22") (pinfunction "RB9_P$22") (pintype "bidirectional"))
    )
    (net (code "44") (name "/U1CTS") (class "Default")
      (node (ref "J10") (pin "CTS") (pinfunction "CTS_CTS") (pintype "bidirectional"))
      (node (ref "R19") (pin "R4A") (pinfunction "R4A_R4A") (pintype "passive"))
      (node (ref "U3") (pin "P$46") (pinfunction "RD0/OC1_P$46") (pintype "bidirectional"))
    )
    (net (code "45") (name "/U1RTS") (class "Default")
      (node (ref "J10") (pin "RTS") (pinfunction "RTS_RTS") (pintype "bidirectional"))
      (node (ref "R19") (pin "R1A") (pinfunction "R1A_R1A") (pintype "passive"))
      (node (ref "U3") (pin "P$52") (pinfunction "RD4/OC5_P$52") (pintype "bidirectional"))
    )
    (net (code "46") (name "/U1RX") (class "Default")
      (node (ref "J10") (pin "RX") (pinfunction "RX_RX") (pintype "bidirectional"))
      (node (ref "R19") (pin "R2A") (pinfunction "R2A_R2A") (pintype "passive"))
      (node (ref "U3") (pin "P$50") (pinfunction "RD2/U1RX_P$50") (pintype "bidirectional"))
    )
    (net (code "47") (name "/U1TX") (class "Default")
      (node (ref "J10") (pin "TX") (pinfunction "TX_TX") (pintype "bidirectional"))
      (node (ref "R19") (pin "R3A") (pinfunction "R3A_R3A") (pintype "passive"))
      (node (ref "U3") (pin "P$51") (pinfunction "RD3/U1TX_P$51") (pintype "bidirectional"))
    )
    (net (code "48") (name "/USBID") (class "Default")
      (node (ref "R6") (pin "2") (pinfunction "2_2") (pintype "passive"))
      (node (ref "U25") (pin "4") (pinfunction "4_4") (pintype "bidirectional"))
      (node (ref "U3") (pin "P$33") (pinfunction "USBID_P$33") (pintype "bidirectional"))
    )
    (net (code "49") (name "/VBUS") (class "Default")
      (node (ref "D1") (pin "A") (pinfunction "A_A") (pintype "passive"))
      (node (ref "U25") (pin "1") (pinfunction "1_1") (pintype "bidirectional"))
    )
    (net (code "50") (name "DGND") (class "Default")
      (node (ref "B1") (pin "1") (pinfunction "1_1") (pintype "passive"))
      (node (ref "C10") (pin "-") (pinfunction "-_-") (pintype "passive"))
      (node (ref "C11") (pin "2") (pinfunction "2_2") (pintype "passive"))
      (node (ref "C12") (pin "2") (pinfunction "2_2") (pintype "passive"))
      (node (ref "C13") (pin "2") (pinfunction "2_2") (pintype "passive"))
      (node (ref "C14") (pin "2") (pinfunction "2_2") (pintype "passive"))
      (node (ref "C15") (pin "2") (pinfunction "2_2") (pintype "passive"))
      (node (ref "C18") (pin "2") (pinfunction "2_2") (pintype "passive"))
      (node (ref "C2") (pin "2") (pinfunction "2_2") (pintype "passive"))
      (node (ref "C20") (pin "2") (pinfunction "2_2") (pintype "passive"))
      (node (ref "C21") (pin "2") (pinfunction "2_2") (pintype "passive"))
      (node (ref "C25") (pin "2") (pinfunction "2_2") (pintype "passive"))
      (node (ref "C26") (pin "2") (pinfunction "2_2") (pintype "passive"))
      (node (ref "C3") (pin "2") (pinfunction "2_2") (pintype "passive"))
      (node (ref "C4") (pin "2") (pinfunction "2_2") (pintype "passive"))
      (node (ref "C5") (pin "2") (pinfunction "2_2") (pintype "passive"))
      (node (ref "C6") (pin "2") (pinfunction "2_2") (pintype "passive"))
      (node (ref "C7") (pin "-") (pinfunction "-_-") (pintype "passive"))
      (node (ref "C8") (pin "-") (pinfunction "-_-") (pintype "passive"))
      (node (ref "C9") (pin "2") (pinfunction "2_2") (pintype "passive"))
      (node (ref "DGND") (pin "PP") (pinfunction "TP_PP") (pintype "input"))
      (node (ref "IC1") (pin "2") (pinfunction "GND_2") (pintype "bidirectional"))
      (node (ref "IC2") (pin "2") (pinfunction "GND_2") (pintype "bidirectional"))
      (node (ref "IC3") (pin "2") (pinfunction "GND_2") (pintype "bidirectional"))
      (node (ref "IC4") (pin "2") (pinfunction "GND_2") (pintype "bidirectional"))
      (node (ref "J1") (pin "15") (pinfunction "GND_15") (pintype "bidirectional"))
      (node (ref "J1") (pin "17") (pinfunction "GND_17") (pintype "bidirectional"))
      (node (ref "J1") (pin "18") (pinfunction "GND_18") (pintype "bidirectional"))
      (node (ref "J1") (pin "19") (pinfunction "GND_19") (pintype "bidirectional"))
      (node (ref "J1") (pin "24") (pinfunction "GND_24") (pintype "bidirectional"))
      (node (ref "J1") (pin "3") (pinfunction "GND_3") (pintype "bidirectional"))
      (node (ref "J1") (pin "5") (pinfunction "GND_5") (pintype "bidirectional"))
      (node (ref "J1") (pin "7") (pinfunction "GND_7") (pintype "bidirectional"))
      (node (ref "J10") (pin "GND") (pinfunction "GND_GND") (pintype "bidirectional"))
      (node (ref "J10") (pin "GND1") (pinfunction "GND1_GND1") (pintype "bidirectional"))
      (node (ref "J12") (pin "10") (pinfunction "10_10") (pintype "bidirectional"))
      (node (ref "J12") (pin "12") (pinfunction "12_12") (pintype "bidirectional"))
      (node (ref "J13") (pin "10") (pinfunction "10_10") (pintype "bidirectional"))
      (node (ref "J13") (pin "12") (pinfunction "12_12") (pintype "bidirectional"))
      (node (ref "J14") (pin "10") (pinfunction "10_10") (pintype "bidirectional"))
      (node (ref "J14") (pin "12") (pinfunction "12_12") (pintype "bidirectional"))
      (node (ref "J15") (pin "10") (pinfunction "10_10") (pintype "bidirectional"))
      (node (ref "J15") (pin "12") (pinfunction "12_12") (pintype "bidirectional"))
      (node (ref "J6") (pin "10") (pinfunction "10_10") (pintype "bidirectional"))
      (node (ref "J6") (pin "12") (pinfunction "12_12") (pintype "bidirectional"))
      (node (ref "J7") (pin "10") (pinfunction "10_10") (pintype "bidirectional"))
      (node (ref "J7") (pin "12") (pinfunction "12_12") (pintype "bidirectional"))
      (node (ref "J8") (pin "10") (pinfunction "10_10") (pintype "bidirectional"))
      (node (ref "J8") (pin "12") (pinfunction "12_12") (pintype "bidirectional"))
      (node (ref "J9") (pin "10") (pinfunction "10_10") (pintype "bidirectional"))
      (node (ref "J9") (pin "12") (pinfunction "12_12") (pintype "bidirectional"))
      (node (ref "Q1") (pin "2") (pinfunction "E_2") (pintype "bidirectional"))
      (node (ref "Q10") (pin "3") (pinfunction "C_3") (pintype "passive"))
      (node (ref "Q12") (pin "2") (pinfunction "E_2") (pintype "bidirectional"))
      (node (ref "Q14") (pin "3") (pinfunction "C_3") (pintype "passive"))
      (node (ref "Q16") (pin "2") (pinfunction "E_2") (pintype "bidirectional"))
      (node (ref "Q2") (pin "3") (pinfunction "C_3") (pintype "passive"))
      (node (ref "Q4") (pin "2") (pinfunction "E_2") (pintype "bidirectional"))
      (node (ref "Q6") (pin "3") (pinfunction "C_3") (pintype "passive"))
      (node (ref "Q8") (pin "2") (pinfunction "E_2") (pintype "bidirectional"))
      (node (ref "R14") (pin "1") (pinfunction "1_1") (pintype "passive"))
      (node (ref "R2") (pin "1") (pinfunction "1_1") (pintype "passive"))
      (node (ref "R22") (pin "1") (pinfunction "1_1") (pintype "passive"))
      (node (ref "R8") (pin "1") (pinfunction "1_1") (pintype "passive"))
      (node (ref "U$19") (pin "P$2") (pinfunction "P$2_P$2") (pintype "bidirectional"))
      (node (ref "U18") (pin "2") (pinfunction "GND_2") (pintype "bidirectional"))
      (node (ref "U25") (pin "5") (pinfunction "5_5") (pintype "bidirectional"))
      (node (ref "U3") (pin "P$20") (pinfunction "AVSS_P$20") (pintype "bidirectional"))
      (node (ref "U3") (pin "P$25") (pinfunction "VSS1_P$25") (pintype "bidirectional"))
      (node (ref "U3") (pin "P$41") (pinfunction "VSS2_P$41") (pintype "bidirectional"))
      (node (ref "U3") (pin "P$9") (pinfunction "VSS_P$9") (pintype "bidirectional"))
      (node (ref "X1") (pin "3") (pinfunction "S_3") (pintype "passive"))
    )
    (net (code "51") (name "GND") (class "Default")
      (node (ref "B1") (pin "2") (pinfunction "2_2") (pintype "passive"))
      (node (ref "J12") (pin "2") (pinfunction "2_2") (pintype "bidirectional"))
      (node (ref "J12") (pin "4") (pinfunction "4_4") (pintype "bidirectional"))
      (node (ref "J12") (pin "6") (pinfunction "6_6") (pintype "bidirectional"))
      (node (ref "J13") (pin "2") (pinfunction "2_2") (pintype "bidirectional"))
      (node (ref "J13") (pin "4") (pinfunction "4_4") (pintype "bidirectional"))
      (node (ref "J13") (pin "6") (pinfunction "6_6") (pintype "bidirectional"))
      (node (ref "J14") (pin "2") (pinfunction "2_2") (pintype "bidirectional"))
      (node (ref "J14") (pin "4") (pinfunction "4_4") (pintype "bidirectional"))
      (node (ref "J14") (pin "6") (pinfunction "6_6") (pintype "bidirectional"))
      (node (ref "J15") (pin "2") (pinfunction "2_2") (pintype "bidirectional"))
      (node (ref "J15") (pin "4") (pinfunction "4_4") (pintype "bidirectional"))
      (node (ref "J15") (pin "6") (pinfunction "6_6") (pintype "bidirectional"))
      (node (ref "J6") (pin "2") (pinfunction "2_2") (pintype "bidirectional"))
      (node (ref "J6") (pin "4") (pinfunction "4_4") (pintype "bidirectional"))
      (node (ref "J6") (pin "6") (pinfunction "6_6") (pintype "bidirectional"))
      (node (ref "J7") (pin "2") (pinfunction "2_2") (pintype "bidirectional"))
      (node (ref "J7") (pin "4") (pinfunction "4_4") (pintype "bidirectional"))
      (node (ref "J7") (pin "6") (pinfunction "6_6") (pintype "bidirectional"))
      (node (ref "J8") (pin "2") (pinfunction "2_2") (pintype "bidirectional"))
      (node (ref "J8") (pin "4") (pinfunction "4_4") (pintype "bidirectional"))
      (node (ref "J8") (pin "6") (pinfunction "6_6") (pintype "bidirectional"))
      (node (ref "J9") (pin "2") (pinfunction "2_2") (pintype "bidirectional"))
      (node (ref "J9") (pin "4") (pinfunction "4_4") (pintype "bidirectional"))
      (node (ref "J9") (pin "6") (pinfunction "6_6") (pintype "bidirectional"))
      (node (ref "Q13") (pin "1") (pinfunction "S_1") (pintype "passive"))
      (node (ref "Q13") (pin "2") (pinfunction "S_2") (pintype "passive"))
      (node (ref "Q13") (pin "3") (pinfunction "S_3") (pintype "passive"))
      (node (ref "Q17") (pin "1") (pinfunction "S_1") (pintype "passive"))
      (node (ref "Q17") (pin "2") (pinfunction "S_2") (pintype "passive"))
      (node (ref "Q17") (pin "3") (pinfunction "S_3") (pintype "passive"))
      (node (ref "Q5") (pin "1") (pinfunction "S_1") (pintype "passive"))
      (node (ref "Q5") (pin "2") (pinfunction "S_2") (pintype "passive"))
      (node (ref "Q5") (pin "3") (pinfunction "S_3") (pintype "passive"))
      (node (ref "Q9") (pin "1") (pinfunction "S_1") (pintype "passive"))
      (node (ref "Q9") (pin "2") (pinfunction "S_2") (pintype "passive"))
      (node (ref "Q9") (pin "3") (pinfunction "S_3") (pintype "passive"))
    )
    (net (code "52") (name "Net-(IC1A-IN+)") (class "Default")
      (node (ref "IC1") (pin "3") (pinfunction "IN+_3") (pintype "input"))
      (node (ref "J4") (pin "3") (pinfunction "1_3") (pintype "passive"))
      (node (ref "R2") (pin "2") (pinfunction "2_2") (pintype "passive"))
    )
    (net (code "53") (name "Net-(IC1B-VCC)") (class "Default")
      (node (ref "C6") (pin "1") (pinfunction "1_1") (pintype "passive"))
      (node (ref "IC1") (pin "5") (pinfunction "VCC_5") (pintype "bidirectional"))
      (node (ref "R17") (pin "1") (pinfunction "1_1") (pintype "passive"))
    )
    (net (code "54") (name "Net-(IC2A-IN+)") (class "Default")
      (node (ref "IC2") (pin "3") (pinfunction "IN+_3") (pintype "input"))
      (node (ref "J16") (pin "3") (pinfunction "1_3") (pintype "passive"))
      (node (ref "R8") (pin "2") (pinfunction "2_2") (pintype "passive"))
    )
    (net (code "55") (name "Net-(IC2B-VCC)") (class "Default")
      (node (ref "C13") (pin "1") (pinfunction "1_1") (pintype "passive"))
      (node (ref "IC2") (pin "5") (pinfunction "VCC_5") (pintype "bidirectional"))
      (node (ref "R7") (pin "1") (pinfunction "1_1") (pintype "passive"))
    )
    (net (code "56") (name "Net-(IC3A-IN+)") (class "Default")
      (node (ref "IC3") (pin "3") (pinfunction "IN+_3") (pintype "input"))
      (node (ref "J2") (pin "3") (pinfunction "1_3") (pintype "passive"))
      (node (ref "R14") (pin "2") (pinfunction "2_2") (pintype "passive"))
    )
    (net (code "57") (name "Net-(IC3B-VCC)") (class "Default")
      (node (ref "C20") (pin "1") (pinfunction "1_1") (pintype "passive"))
      (node (ref "IC3") (pin "5") (pinfunction "VCC_5") (pintype "bidirectional"))
      (node (ref "R13") (pin "1") (pinfunction "1_1") (pintype "passive"))
    )
    (net (code "58") (name "Net-(IC4A-IN+)") (class "Default")
      (node (ref "IC4") (pin "3") (pinfunction "IN+_3") (pintype "input"))
      (node (ref "J3") (pin "3") (pinfunction "1_3") (pintype "passive"))
      (node (ref "R22") (pin "2") (pinfunction "2_2") (pintype "passive"))
    )
    (net (code "59") (name "Net-(IC4B-VCC)") (class "Default")
      (node (ref "C25") (pin "1") (pinfunction "1_1") (pintype "passive"))
      (node (ref "IC4") (pin "5") (pinfunction "VCC_5") (pintype "bidirectional"))
      (node (ref "R21") (pin "1") (pinfunction "1_1") (pintype "passive"))
    )
    (net (code "60") (name "Net-(J1-PS_ON)") (class "Default")
      (node (ref "J1") (pin "16") (pinfunction "PS_ON_16") (pintype "bidirectional"))
      (node (ref "Q1") (pin "3") (pinfunction "C_3") (pintype "bidirectional"))
      (node (ref "R20") (pin "1") (pinfunction "1_1") (pintype "passive"))
    )
    (net (code "61") (name "Net-(J2D-1)") (class "Default")
      (node (ref "C21") (pin "1") (pinfunction "1_1") (pintype "passive"))
      (node (ref "J2") (pin "4") (pinfunction "1_4") (pintype "passive"))
      (node (ref "R15") (pin "1") (pinfunction "1_1") (pintype "passive"))
    )
    (net (code "62") (name "Net-(J3D-1)") (class "Default")
      (node (ref "C26") (pin "1") (pinfunction "1_1") (pintype "passive"))
      (node (ref "J3") (pin "4") (pinfunction "1_4") (pintype "passive"))
      (node (ref "R23") (pin "1") (pinfunction "1_1") (pintype "passive"))
    )
    (net (code "63") (name "Net-(J4D-1)") (class "Default")
      (node (ref "C5") (pin "1") (pinfunction "1_1") (pintype "passive"))
      (node (ref "J4") (pin "4") (pinfunction "1_4") (pintype "passive"))
      (node (ref "R3") (pin "1") (pinfunction "1_1") (pintype "passive"))
    )
    (net (code "64") (name "Net-(J16D-1)") (class "Default")
      (node (ref "C18") (pin "1") (pinfunction "1_1") (pintype "passive"))
      (node (ref "J16") (pin "4") (pinfunction "1_4") (pintype "passive"))
      (node (ref "R9") (pin "1") (pinfunction "1_1") (pintype "passive"))
    )
    (net (code "65") (name "Net-(Q2-B)") (class "Default")
      (node (ref "Q2") (pin "1") (pinfunction "B_1") (pintype "passive"))
      (node (ref "Q3") (pin "1") (pinfunction "B_1") (pintype "bidirectional"))
      (node (ref "Q4") (pin "3") (pinfunction "C_3") (pintype "bidirectional"))
      (node (ref "R1") (pin "1") (pinfunction "1_1") (pintype "passive"))
    )
    (net (code "66") (name "Net-(Q2-E)") (class "Default")
      (node (ref "Q2") (pin "2") (pinfunction "E_2") (pintype "passive"))
      (node (ref "Q3") (pin "2") (pinfunction "E_2") (pintype "bidirectional"))
      (node (ref "Q5") (pin "4") (pinfunction "G_4") (pintype "passive"))
    )
    (net (code "67") (name "Net-(Q4-B)") (class "Default")
      (node (ref "C24") (pin "1") (pinfunction "1_1") (pintype "passive"))
      (node (ref "Q4") (pin "1") (pinfunction "B_1") (pintype "bidirectional"))
      (node (ref "R10") (pin "1") (pinfunction "1_1") (pintype "passive"))
    )
    (net (code "68") (name "Net-(Q6-B)") (class "Default")
      (node (ref "Q6") (pin "1") (pinfunction "B_1") (pintype "passive"))
      (node (ref "Q7") (pin "1") (pinfunction "B_1") (pintype "bidirectional"))
      (node (ref "Q8") (pin "3") (pinfunction "C_3") (pintype "bidirectional"))
      (node (ref "R11") (pin "1") (pinfunction "1_1") (pintype "passive"))
    )
    (net (code "69") (name "Net-(Q6-E)") (class "Default")
      (node (ref "Q6") (pin "2") (pinfunction "E_2") (pintype "passive"))
      (node (ref "Q7") (pin "2") (pinfunction "E_2") (pintype "bidirectional"))
      (node (ref "Q9") (pin "4") (pinfunction "G_4") (pintype "passive"))
    )
    (net (code "70") (name "Net-(Q8-B)") (class "Default")
      (node (ref "C19") (pin "1") (pinfunction "1_1") (pintype "passive"))
      (node (ref "Q8") (pin "1") (pinfunction "B_1") (pintype "bidirectional"))
      (node (ref "R12") (pin "1") (pinfunction "1_1") (pintype "passive"))
    )
    (net (code "71") (name "Net-(Q10-B)") (class "Default")
      (node (ref "Q10") (pin "1") (pinfunction "B_1") (pintype "passive"))
      (node (ref "Q11") (pin "1") (pinfunction "B_1") (pintype "bidirectional"))
      (node (ref "Q12") (pin "3") (pinfunction "C_3") (pintype "bidirectional"))
      (node (ref "R16") (pin "1") (pinfunction "1_1") (pintype "passive"))
    )
    (net (code "72") (name "Net-(Q10-E)") (class "Default")
      (node (ref "Q10") (pin "2") (pinfunction "E_2") (pintype "passive"))
      (node (ref "Q11") (pin "2") (pinfunction "E_2") (pintype "bidirectional"))
      (node (ref "Q13") (pin "4") (pinfunction "G_4") (pintype "passive"))
    )
    (net (code "73") (name "Net-(Q12-B)") (class "Default")
      (node (ref "C22") (pin "1") (pinfunction "1_1") (pintype "passive"))
      (node (ref "Q12") (pin "1") (pinfunction "B_1") (pintype "bidirectional"))
      (node (ref "R18") (pin "1") (pinfunction "1_1") (pintype "passive"))
    )
    (net (code "74") (name "Net-(Q14-B)") (class "Default")
      (node (ref "Q14") (pin "1") (pinfunction "B_1") (pintype "passive"))
      (node (ref "Q15") (pin "1") (pinfunction "B_1") (pintype "bidirectional"))
      (node (ref "Q16") (pin "3") (pinfunction "C_3") (pintype "bidirectional"))
      (node (ref "R24") (pin "1") (pinfunction "1_1") (pintype "passive"))
    )
    (net (code "75") (name "Net-(Q14-E)") (class "Default")
      (node (ref "Q14") (pin "2") (pinfunction "E_2") (pintype "passive"))
      (node (ref "Q15") (pin "2") (pinfunction "E_2") (pintype "bidirectional"))
      (node (ref "Q17") (pin "4") (pinfunction "G_4") (pintype "passive"))
    )
    (net (code "76") (name "Net-(Q16-B)") (class "Default")
      (node (ref "C27") (pin "1") (pinfunction "1_1") (pintype "passive"))
      (node (ref "Q16") (pin "1") (pinfunction "B_1") (pintype "bidirectional"))
      (node (ref "R25") (pin "1") (pinfunction "1_1") (pintype "passive"))
    )
    (net (code "77") (name "Net-(U3-RC12{slash}OSC1)") (class "Default")
      (node (ref "C2") (pin "1") (pinfunction "1_1") (pintype "passive"))
      (node (ref "U3") (pin "P$39") (pinfunction "RC12/OSC1_P$39") (pintype "bidirectional"))
      (node (ref "X2") (pin "P$1") (pinfunction "P$1_P$1") (pintype "bidirectional"))
    )
    (net (code "78") (name "Net-(U3-RC15{slash}OSC2)") (class "Default")
      (node (ref "C3") (pin "1") (pinfunction "1_1") (pintype "passive"))
      (node (ref "U3") (pin "P$40") (pinfunction "RC15/OSC2_P$40") (pintype "bidirectional"))
      (node (ref "X2") (pin "P$3") (pinfunction "P$2_P$3") (pintype "bidirectional"))
    )
    (net (code "79") (name "Net-(U3-VCAP)") (class "Default")
      (node (ref "C10") (pin "+") (pinfunction "+_+") (pintype "passive"))
      (node (ref "C11") (pin "1") (pinfunction "1_1") (pintype "passive"))
      (node (ref "U3") (pin "P$56") (pinfunction "VCAP_P$56") (pintype "bidirectional"))
    )
    (net (code "80") (name "Net-(U18-BYPASS)") (class "Default")
      (node (ref "C9") (pin "1") (pinfunction "1_1") (pintype "passive"))
      (node (ref "U18") (pin "4") (pinfunction "BYPASS_4") (pintype "bidirectional"))
    )
    (net (code "81") (name "Net-(U18-EN)") (class "Default")
      (node (ref "R4") (pin "2") (pinfunction "2_2") (pintype "passive"))
      (node (ref "U18") (pin "3") (pinfunction "EN_3") (pintype "bidirectional"))
    )
    (net (code "82") (name "VDD") (class "Default")
      (node (ref "U$19") (pin "P$1") (pinfunction "P$1_P$1") (pintype "bidirectional"))
    )
    (net (code "83") (name "unconnected-(J1--12V-Pad14)") (class "Default")
      (node (ref "J1") (pin "14") (pinfunction "-12V_14") (pintype "bidirectional"))
    )
    (net (code "84") (name "unconnected-(J1-NC-Pad20)") (class "Default")
      (node (ref "J1") (pin "20") (pinfunction "NC_20") (pintype "bidirectional"))
    )
    (net (code "85") (name "unconnected-(J1-PWR_OK-Pad8)") (class "Default")
      (node (ref "J1") (pin "8") (pinfunction "PWR_OK_8") (pintype "bidirectional"))
    )
    (net (code "86") (name "unconnected-(U3-RB11-PadP$24)") (class "Default")
      (node (ref "U3") (pin "P$24") (pinfunction "RB11_P$24") (pintype "bidirectional"))
    )
    (net (code "87") (name "unconnected-(U3-RB13-PadP$28)") (class "Default")
      (node (ref "U3") (pin "P$28") (pinfunction "RB13_P$28") (pintype "bidirectional"))
    )
    (net (code "88") (name "unconnected-(U3-RB14-PadP$29)") (class "Default")
      (node (ref "U3") (pin "P$29") (pinfunction "RB14_P$29") (pintype "bidirectional"))
    )
    (net (code "89") (name "unconnected-(U3-RB15-PadP$30)") (class "Default")
      (node (ref "U3") (pin "P$30") (pinfunction "RB15_P$30") (pintype "bidirectional"))
    )
    (net (code "90") (name "unconnected-(U3-RC13-PadP$47)") (class "Default")
      (node (ref "U3") (pin "P$47") (pinfunction "RC13_P$47") (pintype "bidirectional"))
    )
    (net (code "91") (name "unconnected-(U3-RD8-PadP$42)") (class "Default")
      (node (ref "U3") (pin "P$42") (pinfunction "RD8_P$42") (pintype "bidirectional"))
    )
    (net (code "92") (name "unconnected-(U3-RD9-PadP$43)") (class "Default")
      (node (ref "U3") (pin "P$43") (pinfunction "RD9_P$43") (pintype "bidirectional"))
    )
    (net (code "93") (name "unconnected-(U3-RD10-PadP$44)") (class "Default")
      (node (ref "U3") (pin "P$44") (pinfunction "RD10_P$44") (pintype "bidirectional"))
    )
    (net (code "94") (name "unconnected-(U3-RD11-PadP$45)") (class "Default")
      (node (ref "U3") (pin "P$45") (pinfunction "RD11_P$45") (pintype "bidirectional"))
    )
    (net (code "95") (name "unconnected-(U3-RF4{slash}U2RX-PadP$31)") (class "Default")
      (node (ref "U3") (pin "P$31") (pinfunction "RF4/U2RX_P$31") (pintype "bidirectional"))
    )
    (net (code "96") (name "unconnected-(U3-RF5{slash}U2TX-PadP$32)") (class "Default")
      (node (ref "U3") (pin "P$32") (pinfunction "RF5/U2TX_P$32") (pintype "bidirectional"))
    )
    (net (code "97") (name "unconnected-(U3-RG9-PadP$8)") (class "Default")
      (node (ref "U3") (pin "P$8") (pinfunction "RG9_P$8") (pintype "bidirectional"))
    )
    (net (code "98") (name "unconnected-(U25-PadP1)") (class "Default")
      (node (ref "U25") (pin "P1") (pinfunction "P1_P1") (pintype "bidirectional"))
    )
    (net (code "99") (name "unconnected-(U25-PadP2)") (class "Default")
      (node (ref "U25") (pin "P2") (pinfunction "P2_P2") (pintype "bidirectional"))
    )
    (net (code "100") (name "unconnected-(U25-PadP3)") (class "Default")
      (node (ref "U25") (pin "P3") (pinfunction "P3_P3") (pintype "bidirectional"))
    )
    (net (code "101") (name "unconnected-(U25-PadP4)") (class "Default")
      (node (ref "U25") (pin "P4") (pinfunction "P4_P4") (pintype "bidirectional"))
    )
    (net (code "102") (name "unconnected-(X1F-S-Pad6)") (class "Default")
      (node (ref "X1") (pin "6") (pinfunction "S_6") (pintype "passive"))
    )
    (net (code "103") (name "unconnected-(X2-SHIELD-PadP$4)") (class "Default")
      (node (ref "X2") (pin "P$4") (pinfunction "SHIELD_P$4") (pintype "bidirectional"))
    )
  )
)
